# framMega.net
KiCad netlist of a schematic drawn in EAGLE
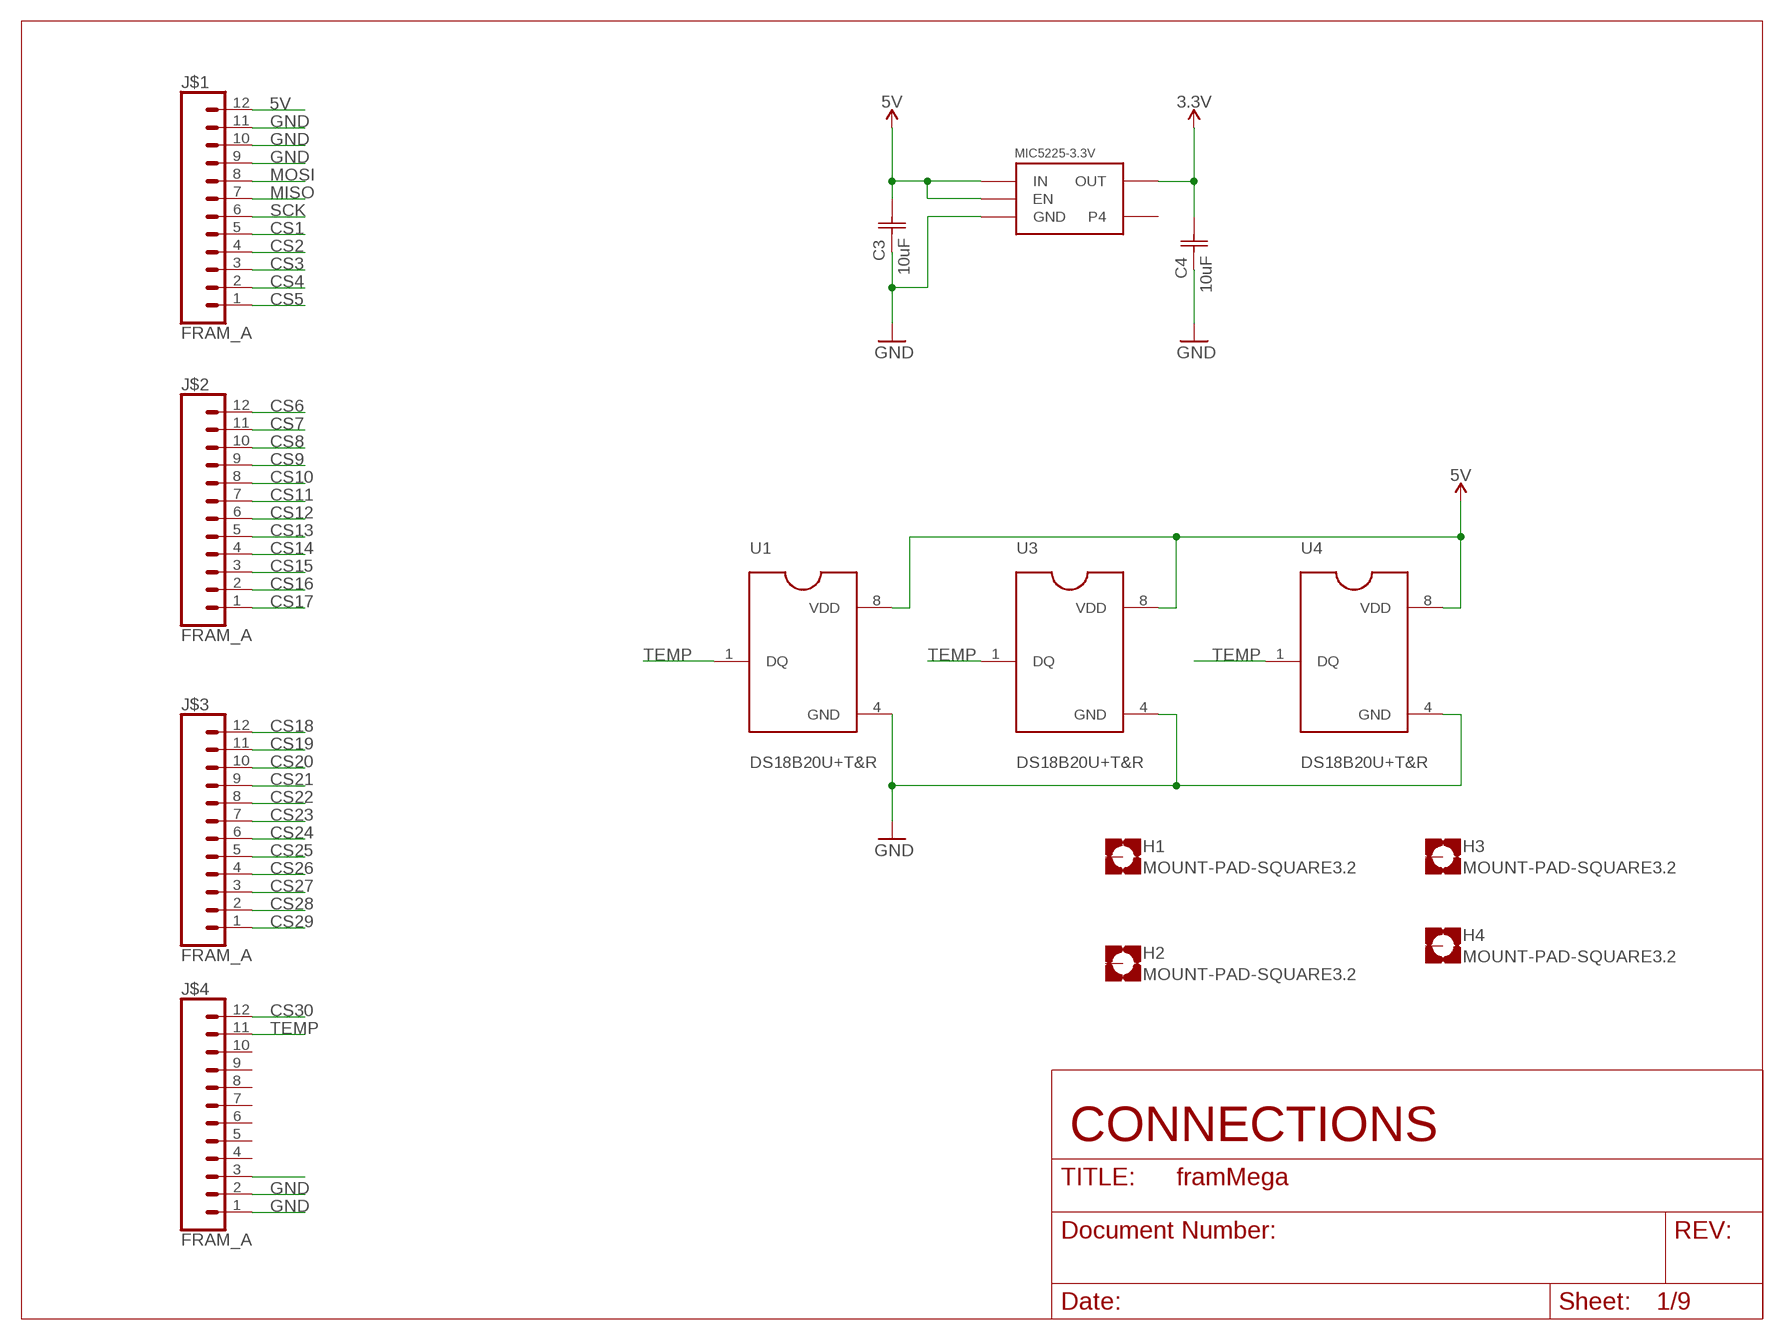
[diagram p0: schematic, sheet 1]
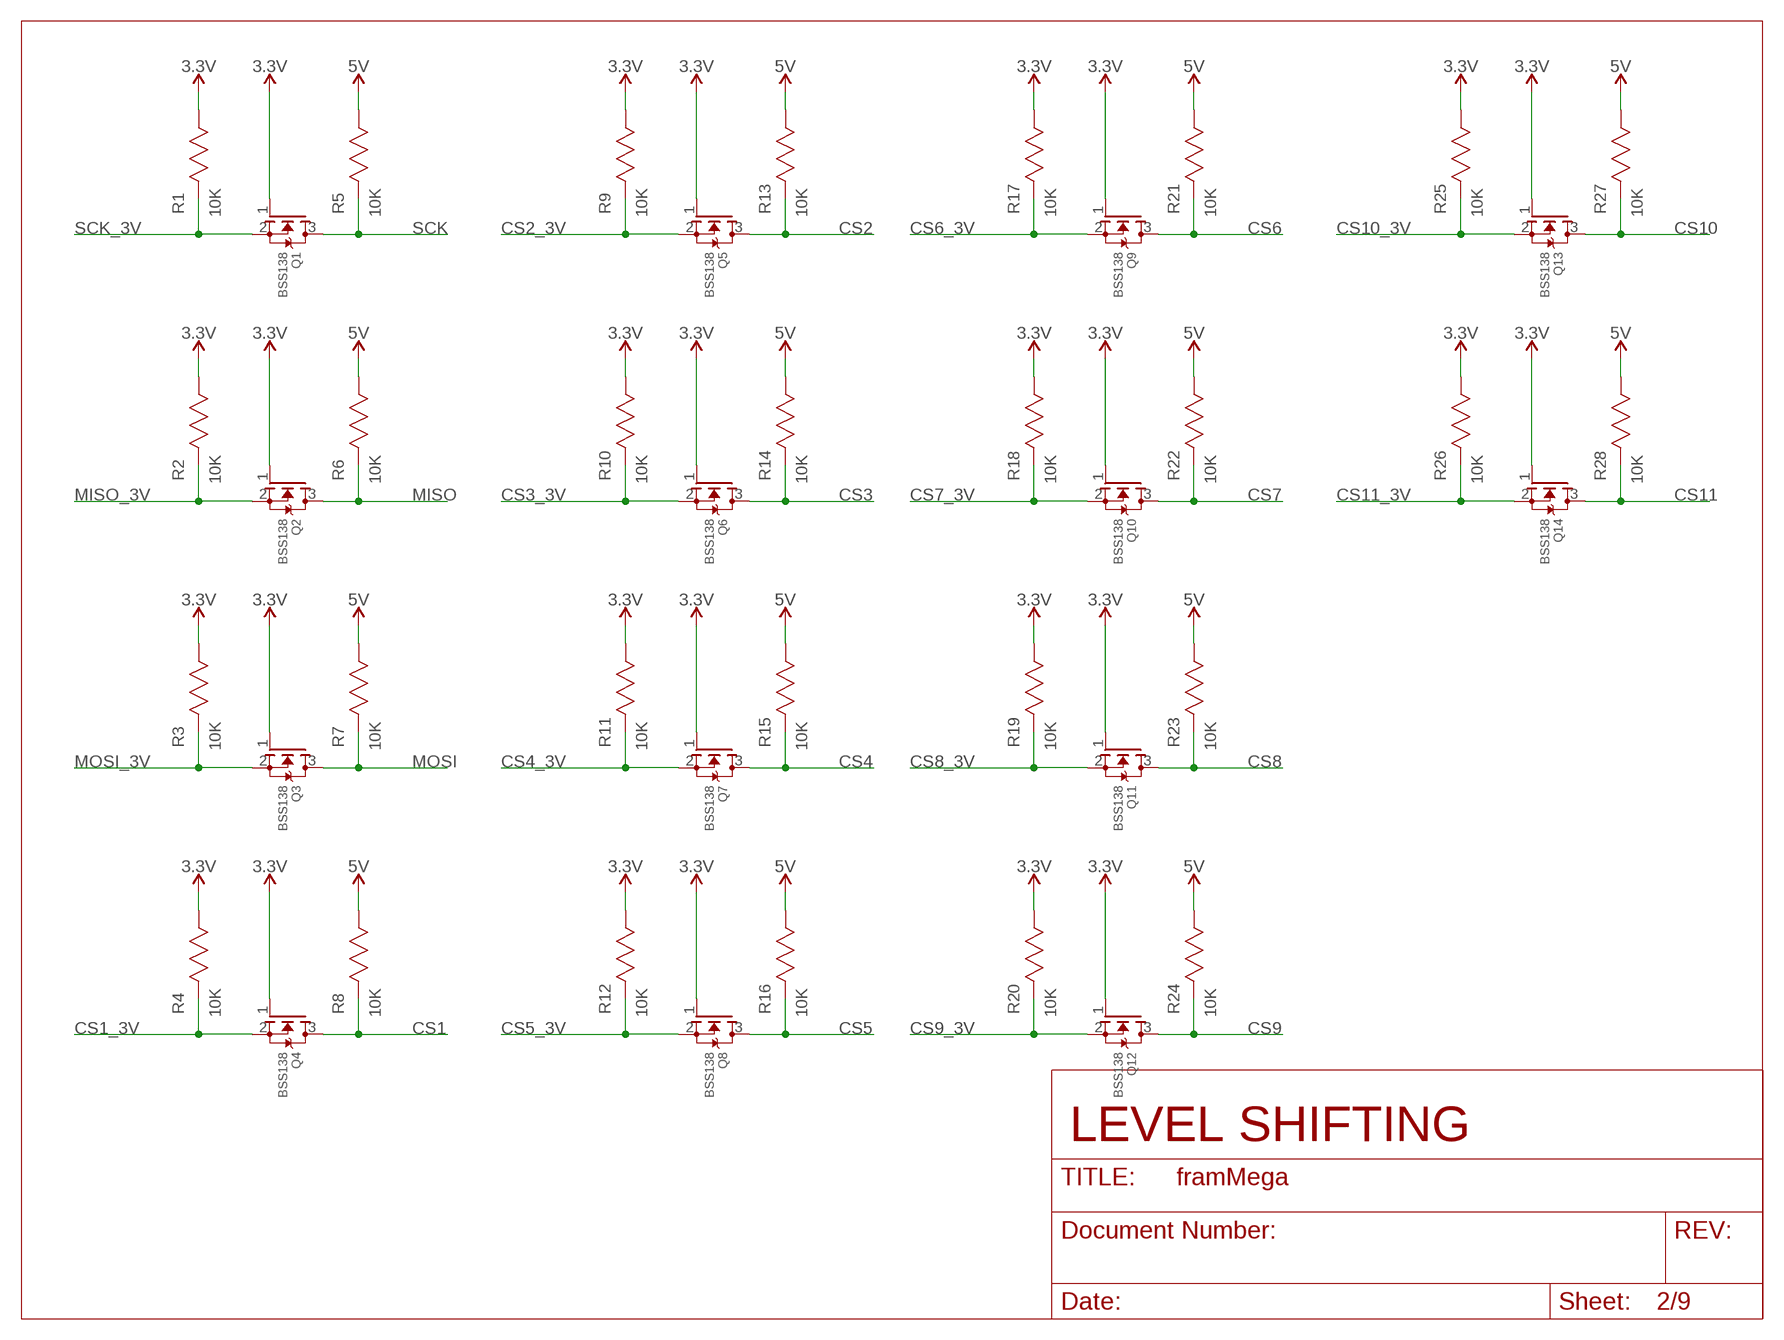
[diagram p1: schematic, sheet 2]
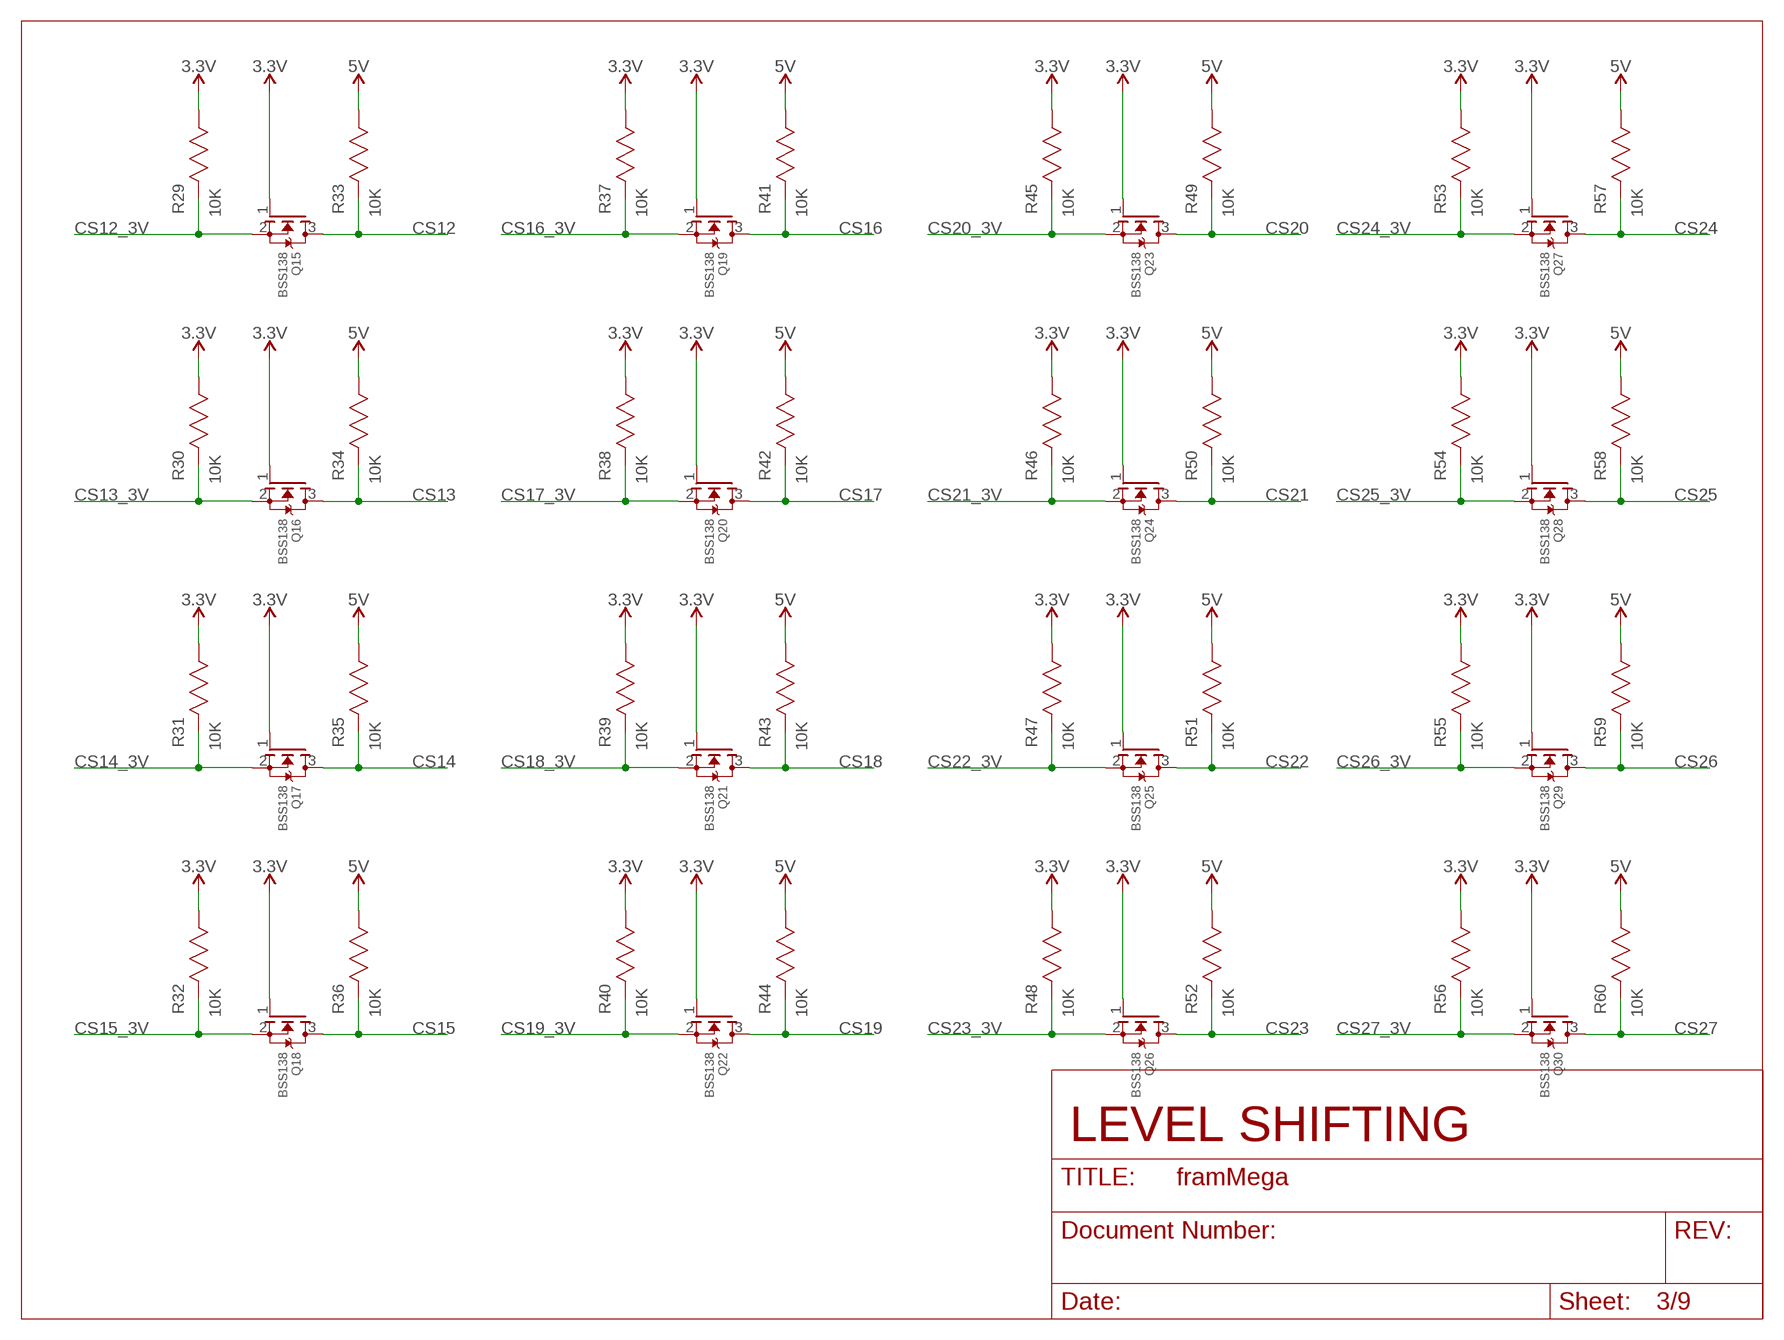
[diagram p2: schematic, sheet 3]
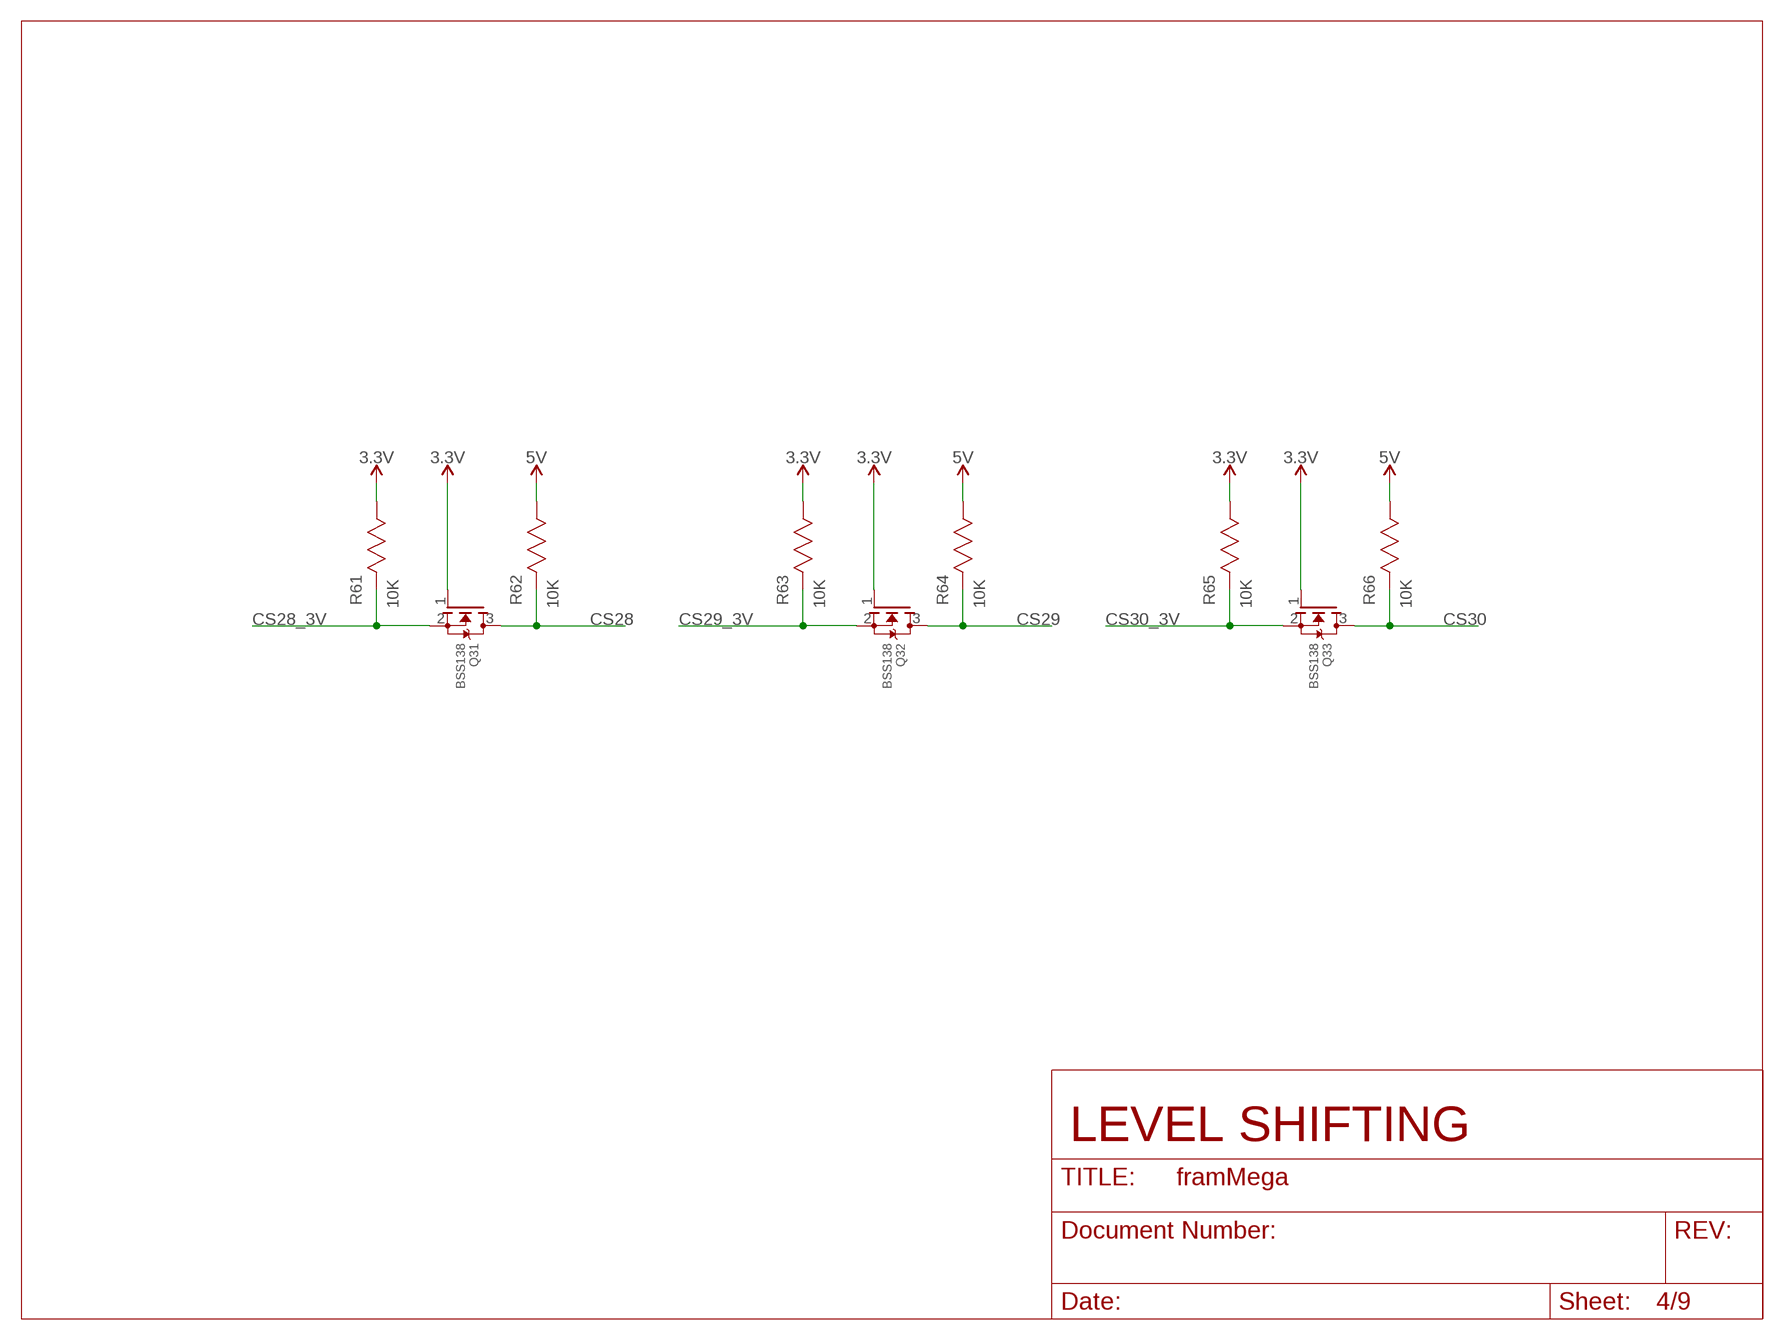
[diagram p3: schematic, sheet 4]
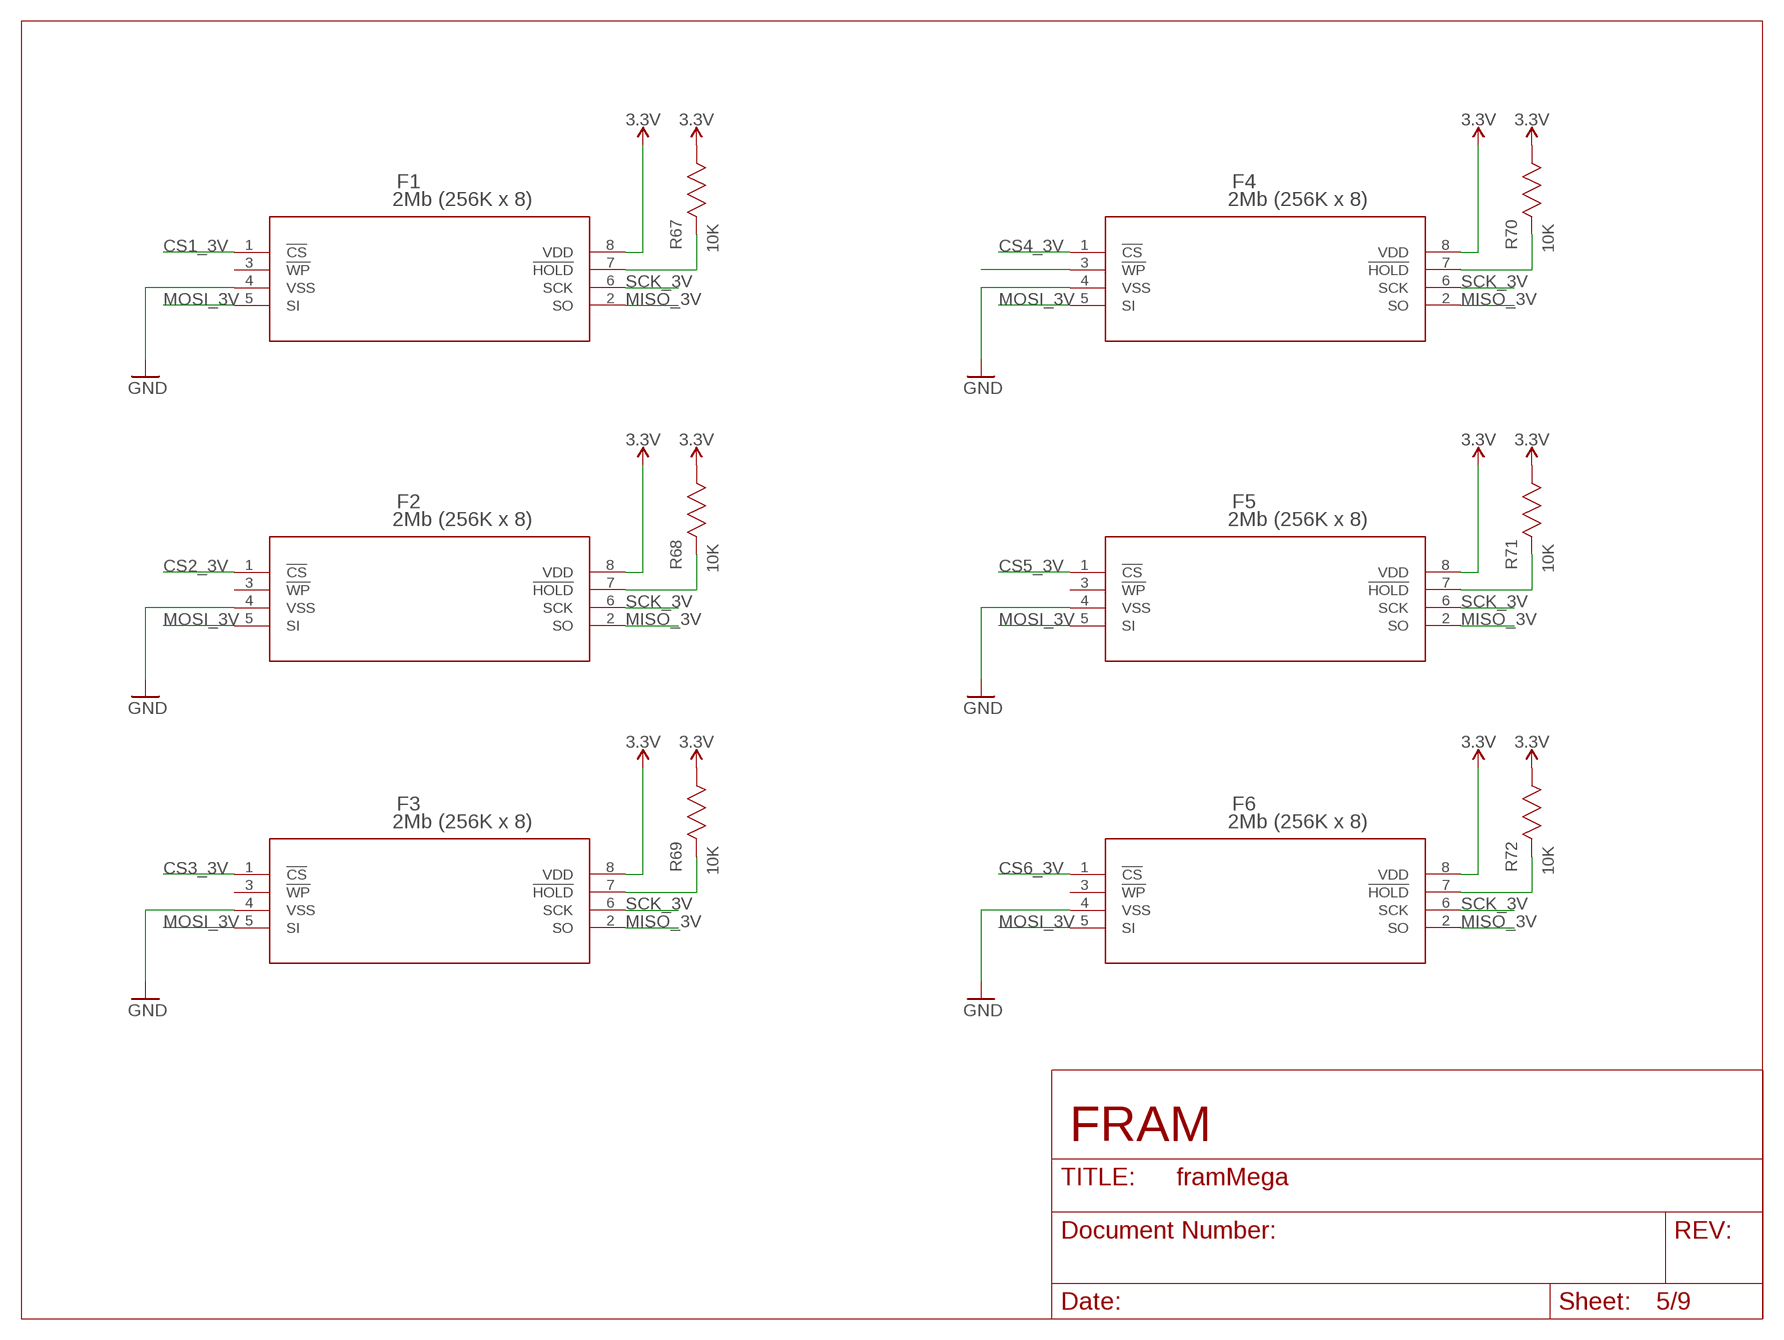
[diagram p4: schematic, sheet 5]
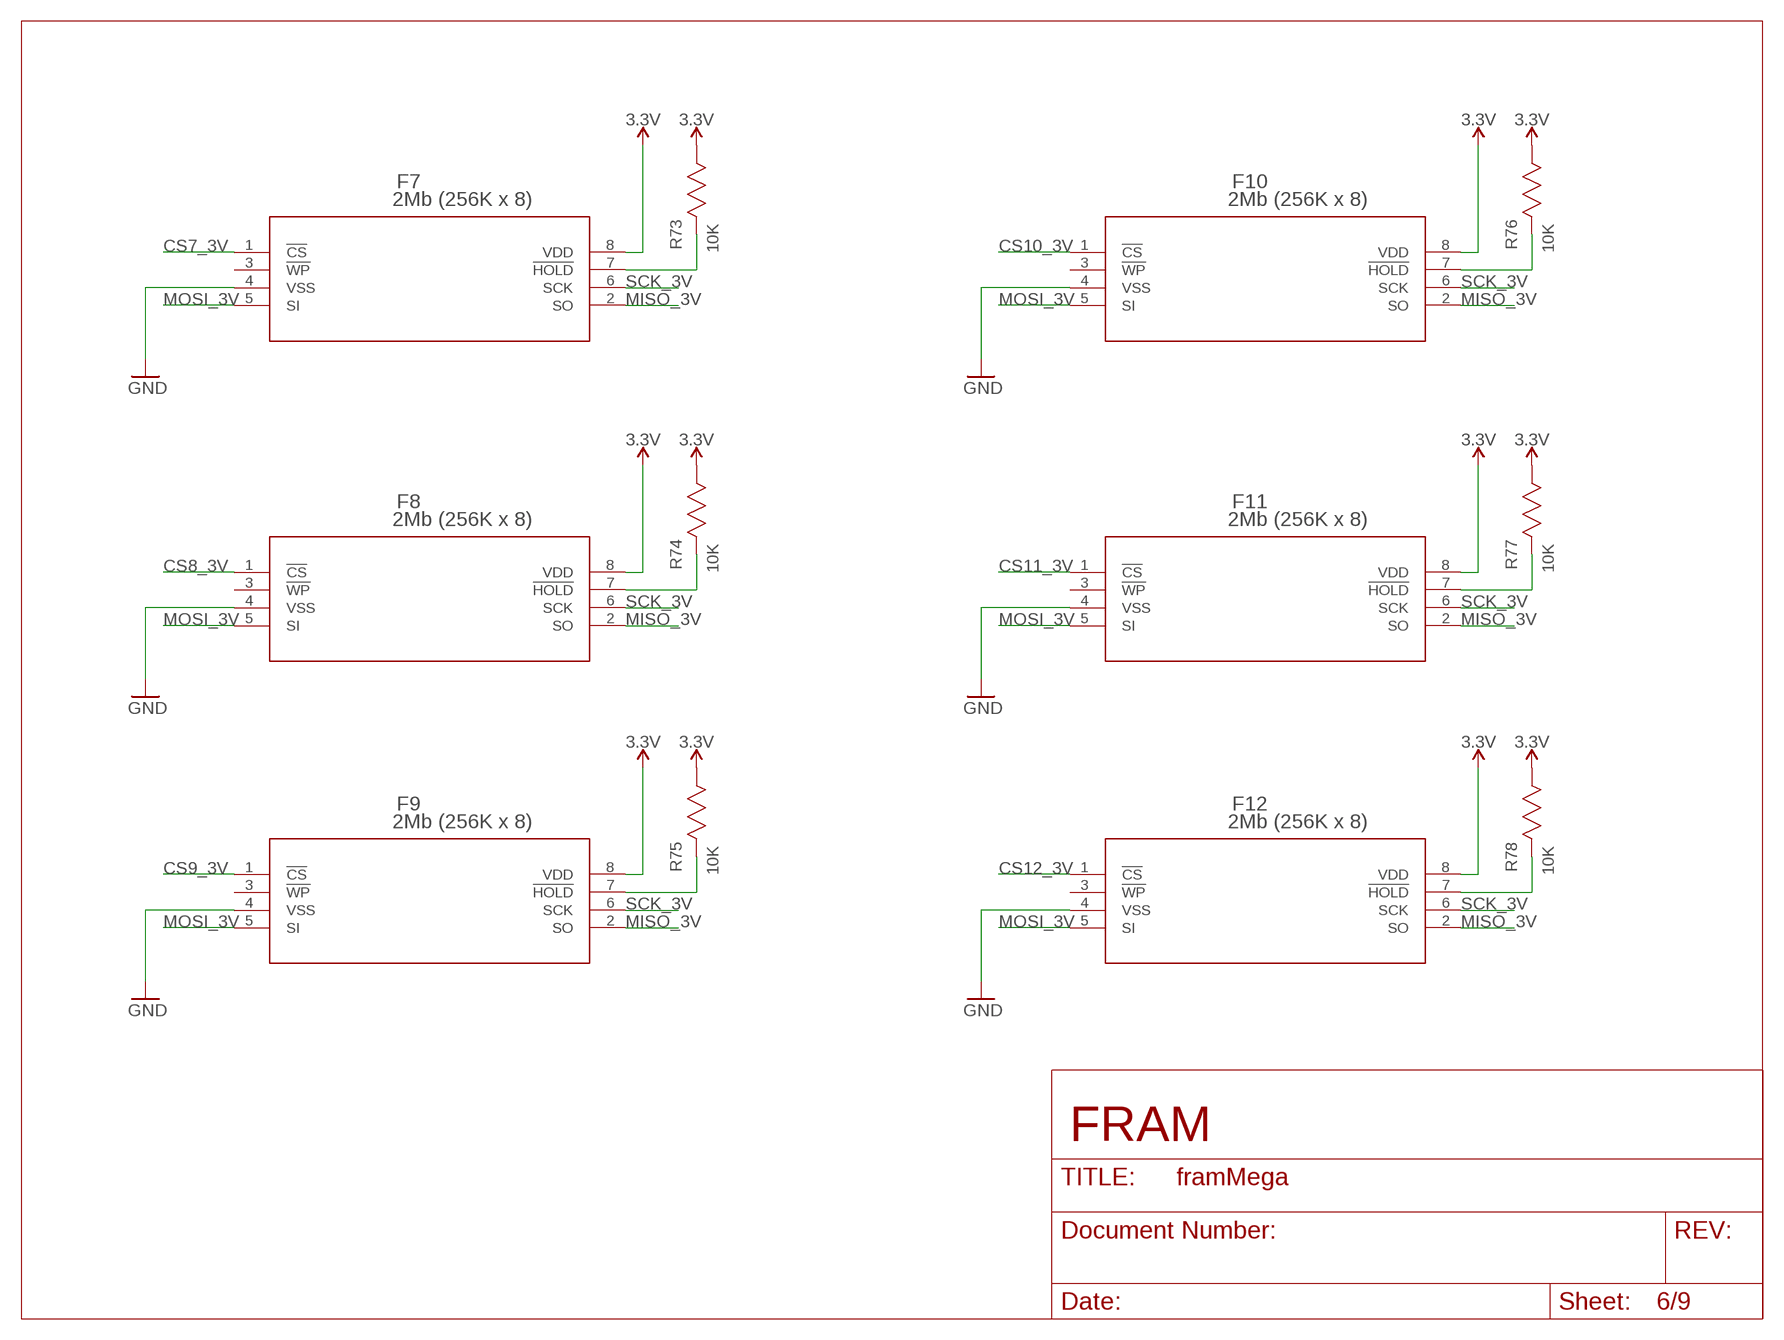
[diagram p5: schematic, sheet 6]
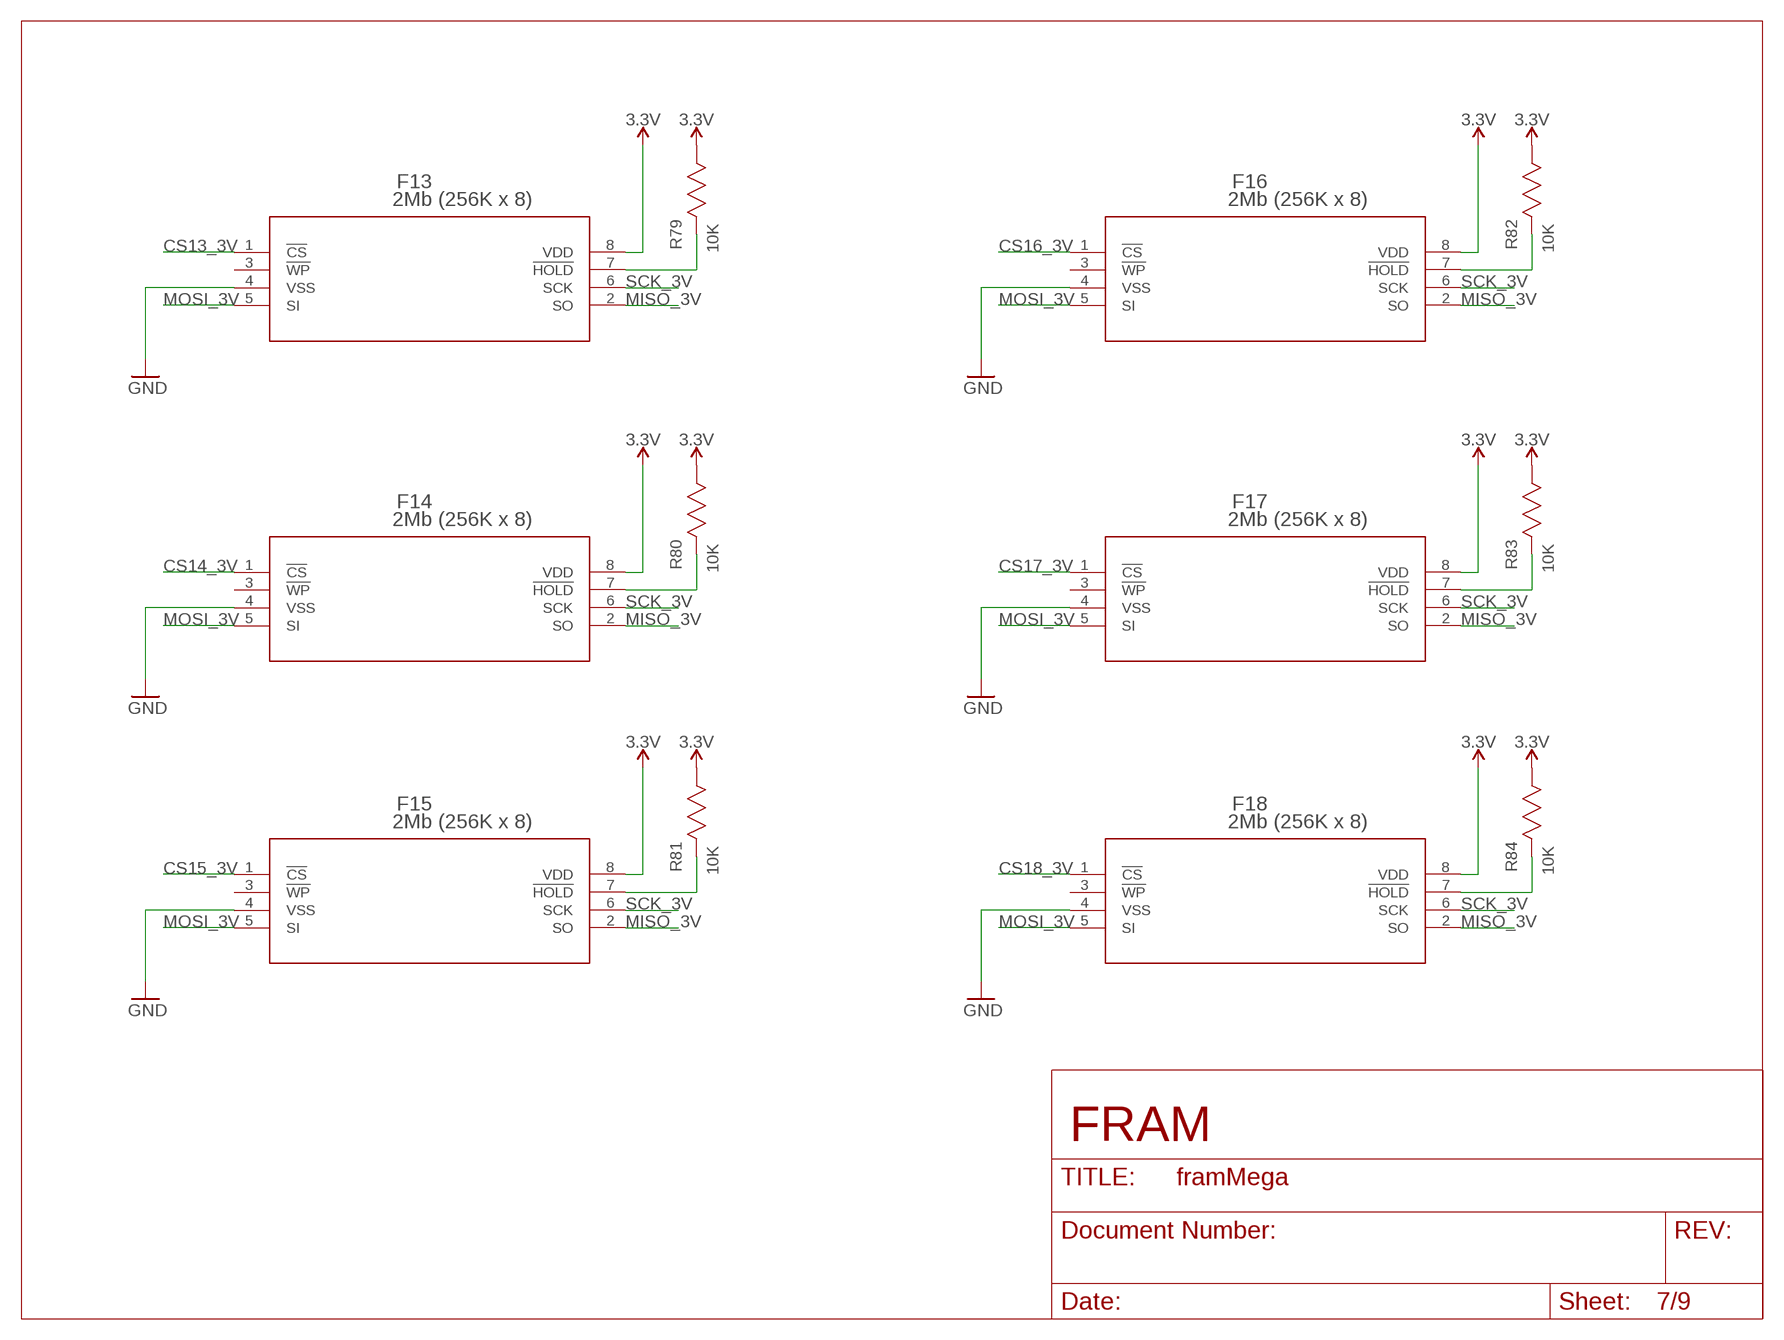
[diagram p6: schematic, sheet 7]
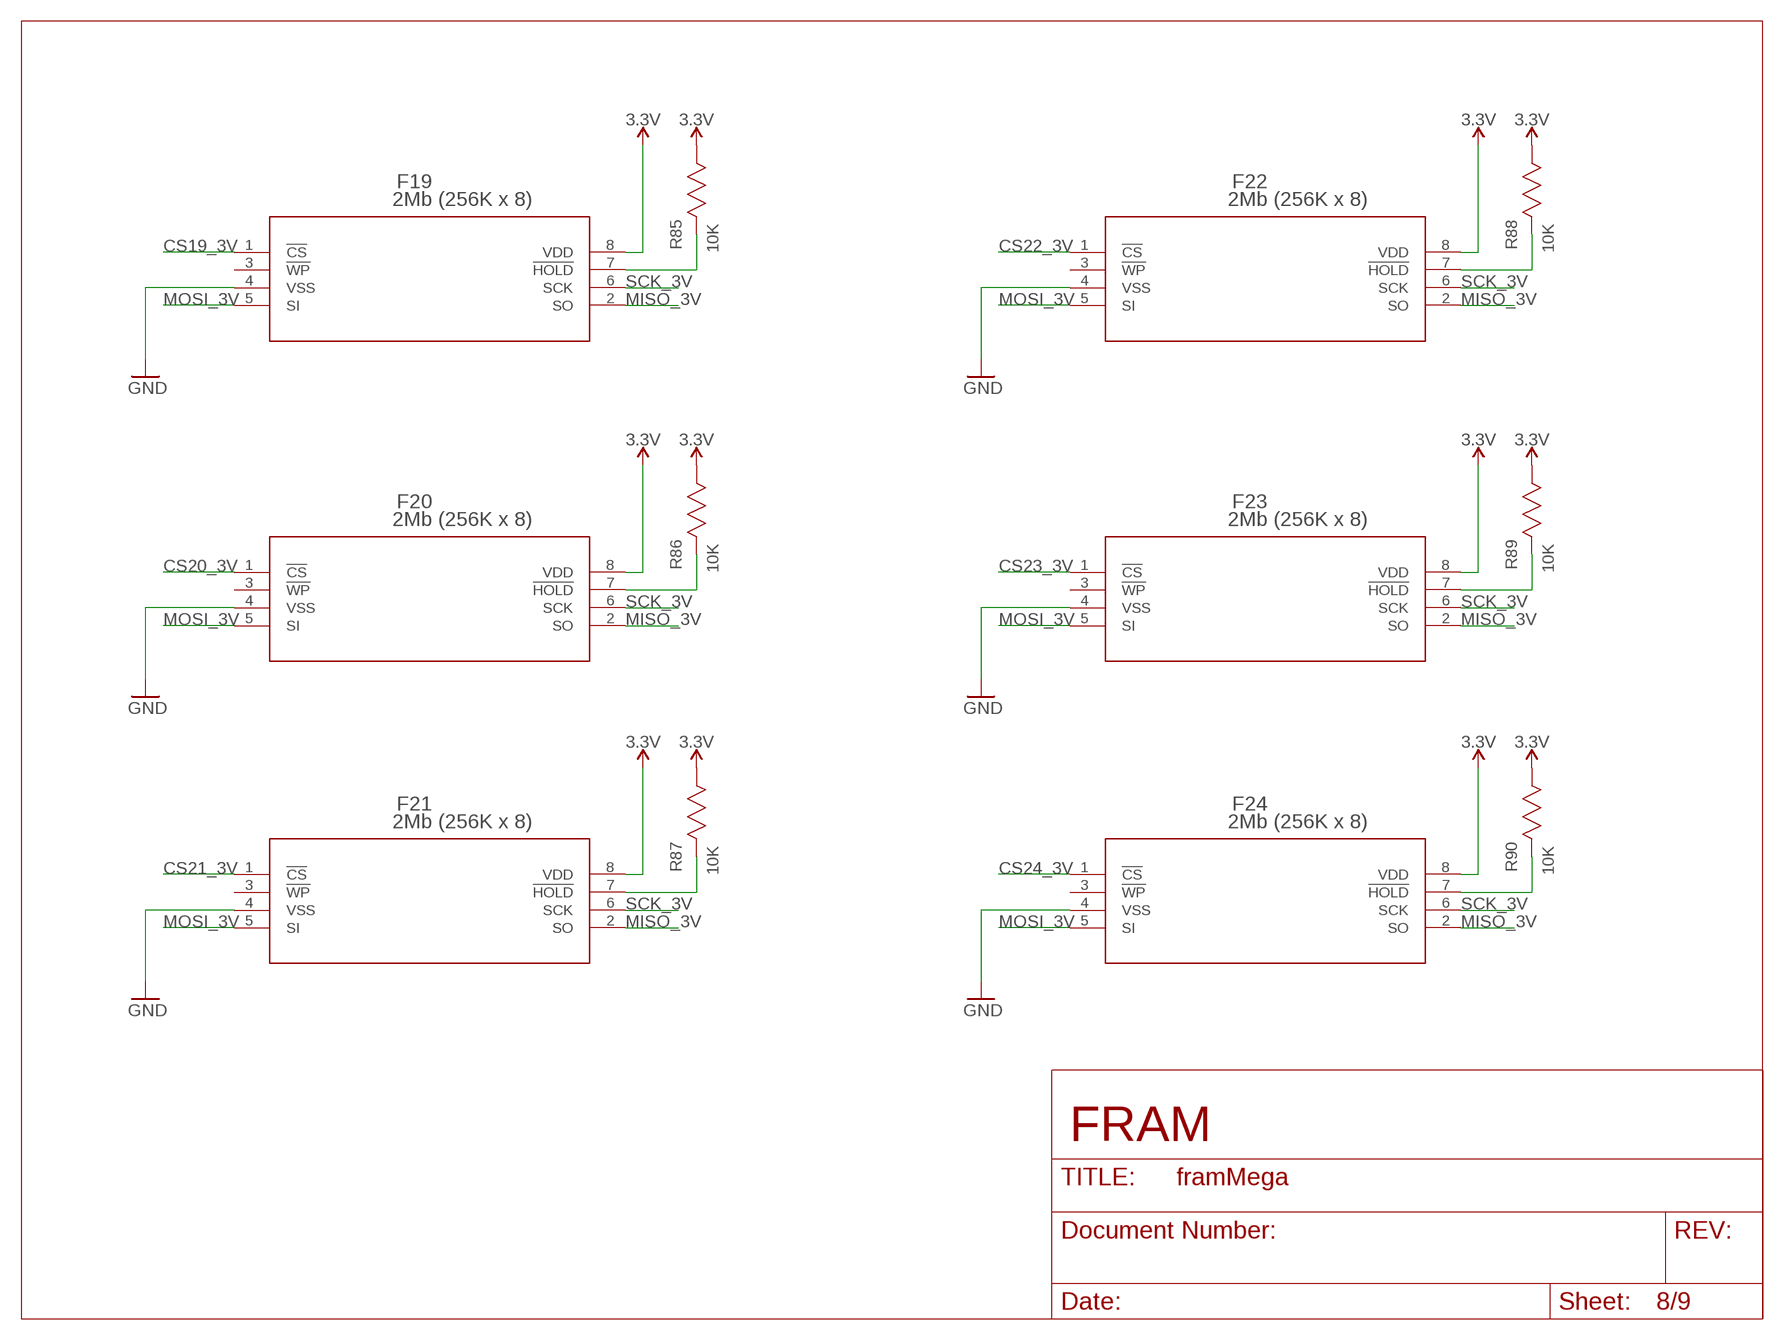
[diagram p7: schematic, sheet 8]
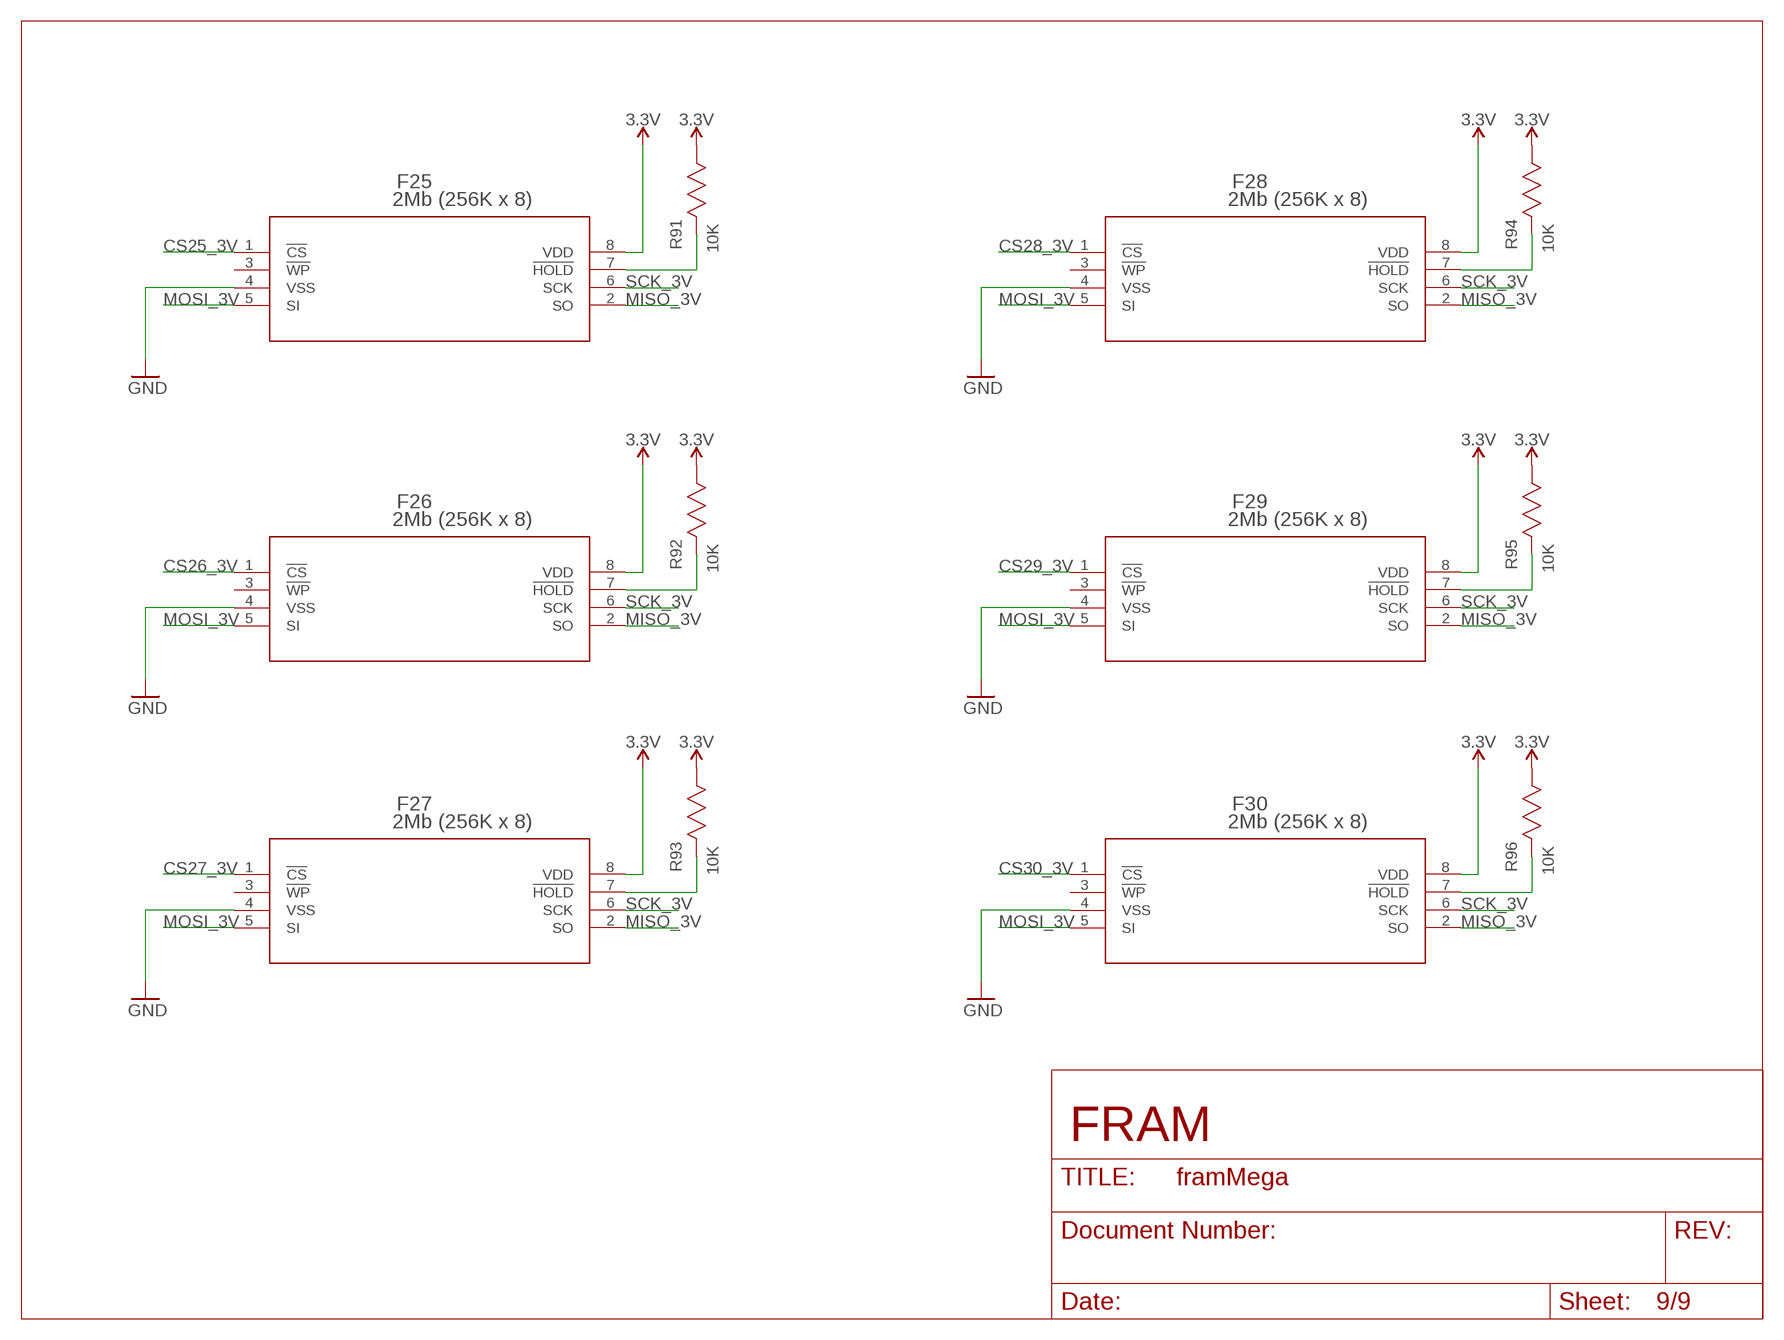
[diagram p8: schematic, sheet 9]

(export (version "E")
  (design (tool "Eeschema 10.0.6"))
  (components
    (comp (ref "Q31")
      (value "BSS138")
      (footprint "eagle-import:SOT23-WIDE")
      (libsource (lib "eagle-import") (part "MOSFET-NWIDE"))
    )
    (comp (ref "Q32")
      (value "BSS138")
      (footprint "eagle-import:SOT23-WIDE")
      (libsource (lib "eagle-import") (part "MOSFET-NWIDE"))
    )
    (comp (ref "Q33")
      (value "BSS138")
      (footprint "eagle-import:SOT23-WIDE")
      (libsource (lib "eagle-import") (part "MOSFET-NWIDE"))
    )
    (comp (ref "R61")
      (value "10K")
      (footprint "eagle-import:RC0603N")
      (libsource (lib "eagle-import") (part "RES_10K"))
    )
    (comp (ref "R62")
      (value "10K")
      (footprint "eagle-import:RC0603N")
      (libsource (lib "eagle-import") (part "RES_10K"))
    )
    (comp (ref "R63")
      (value "10K")
      (footprint "eagle-import:RC0603N")
      (libsource (lib "eagle-import") (part "RES_10K"))
    )
    (comp (ref "R64")
      (value "10K")
      (footprint "eagle-import:RC0603N")
      (libsource (lib "eagle-import") (part "RES_10K"))
    )
    (comp (ref "R65")
      (value "10K")
      (footprint "eagle-import:RC0603N")
      (libsource (lib "eagle-import") (part "RES_10K"))
    )
    (comp (ref "R66")
      (value "10K")
      (footprint "eagle-import:RC0603N")
      (libsource (lib "eagle-import") (part "RES_10K"))
    )
    (comp (ref "Q1")
      (value "BSS138")
      (footprint "eagle-import:SOT23-WIDE")
      (libsource (lib "eagle-import") (part "MOSFET-NWIDE"))
    )
    (comp (ref "Q2")
      (value "BSS138")
      (footprint "eagle-import:SOT23-WIDE")
      (libsource (lib "eagle-import") (part "MOSFET-NWIDE"))
    )
    (comp (ref "Q3")
      (value "BSS138")
      (footprint "eagle-import:SOT23-WIDE")
      (libsource (lib "eagle-import") (part "MOSFET-NWIDE"))
    )
    (comp (ref "Q4")
      (value "BSS138")
      (footprint "eagle-import:SOT23-WIDE")
      (libsource (lib "eagle-import") (part "MOSFET-NWIDE"))
    )
    (comp (ref "Q5")
      (value "BSS138")
      (footprint "eagle-import:SOT23-WIDE")
      (libsource (lib "eagle-import") (part "MOSFET-NWIDE"))
    )
    (comp (ref "Q6")
      (value "BSS138")
      (footprint "eagle-import:SOT23-WIDE")
      (libsource (lib "eagle-import") (part "MOSFET-NWIDE"))
    )
    (comp (ref "Q7")
      (value "BSS138")
      (footprint "eagle-import:SOT23-WIDE")
      (libsource (lib "eagle-import") (part "MOSFET-NWIDE"))
    )
    (comp (ref "Q8")
      (value "BSS138")
      (footprint "eagle-import:SOT23-WIDE")
      (libsource (lib "eagle-import") (part "MOSFET-NWIDE"))
    )
    (comp (ref "Q9")
      (value "BSS138")
      (footprint "eagle-import:SOT23-WIDE")
      (libsource (lib "eagle-import") (part "MOSFET-NWIDE"))
    )
    (comp (ref "Q10")
      (value "BSS138")
      (footprint "eagle-import:SOT23-WIDE")
      (libsource (lib "eagle-import") (part "MOSFET-NWIDE"))
    )
    (comp (ref "Q11")
      (value "BSS138")
      (footprint "eagle-import:SOT23-WIDE")
      (libsource (lib "eagle-import") (part "MOSFET-NWIDE"))
    )
    (comp (ref "Q12")
      (value "BSS138")
      (footprint "eagle-import:SOT23-WIDE")
      (libsource (lib "eagle-import") (part "MOSFET-NWIDE"))
    )
    (comp (ref "Q13")
      (value "BSS138")
      (footprint "eagle-import:SOT23-WIDE")
      (libsource (lib "eagle-import") (part "MOSFET-NWIDE"))
    )
    (comp (ref "Q14")
      (value "BSS138")
      (footprint "eagle-import:SOT23-WIDE")
      (libsource (lib "eagle-import") (part "MOSFET-NWIDE"))
    )
    (comp (ref "R1")
      (value "10K")
      (footprint "eagle-import:RC0603N")
      (libsource (lib "eagle-import") (part "RES_10K"))
    )
    (comp (ref "R2")
      (value "10K")
      (footprint "eagle-import:RC0603N")
      (libsource (lib "eagle-import") (part "RES_10K"))
    )
    (comp (ref "R3")
      (value "10K")
      (footprint "eagle-import:RC0603N")
      (libsource (lib "eagle-import") (part "RES_10K"))
    )
    (comp (ref "R4")
      (value "10K")
      (footprint "eagle-import:RC0603N")
      (libsource (lib "eagle-import") (part "RES_10K"))
    )
    (comp (ref "R5")
      (value "10K")
      (footprint "eagle-import:RC0603N")
      (libsource (lib "eagle-import") (part "RES_10K"))
    )
    (comp (ref "R6")
      (value "10K")
      (footprint "eagle-import:RC0603N")
      (libsource (lib "eagle-import") (part "RES_10K"))
    )
    (comp (ref "R7")
      (value "10K")
      (footprint "eagle-import:RC0603N")
      (libsource (lib "eagle-import") (part "RES_10K"))
    )
    (comp (ref "R8")
      (value "10K")
      (footprint "eagle-import:RC0603N")
      (libsource (lib "eagle-import") (part "RES_10K"))
    )
    (comp (ref "R9")
      (value "10K")
      (footprint "eagle-import:RC0603N")
      (libsource (lib "eagle-import") (part "RES_10K"))
    )
    (comp (ref "R10")
      (value "10K")
      (footprint "eagle-import:RC0603N")
      (libsource (lib "eagle-import") (part "RES_10K"))
    )
    (comp (ref "R11")
      (value "10K")
      (footprint "eagle-import:RC0603N")
      (libsource (lib "eagle-import") (part "RES_10K"))
    )
    (comp (ref "R12")
      (value "10K")
      (footprint "eagle-import:RC0603N")
      (libsource (lib "eagle-import") (part "RES_10K"))
    )
    (comp (ref "R13")
      (value "10K")
      (footprint "eagle-import:RC0603N")
      (libsource (lib "eagle-import") (part "RES_10K"))
    )
    (comp (ref "R14")
      (value "10K")
      (footprint "eagle-import:RC0603N")
      (libsource (lib "eagle-import") (part "RES_10K"))
    )
    (comp (ref "R15")
      (value "10K")
      (footprint "eagle-import:RC0603N")
      (libsource (lib "eagle-import") (part "RES_10K"))
    )
    (comp (ref "R16")
      (value "10K")
      (footprint "eagle-import:RC0603N")
      (libsource (lib "eagle-import") (part "RES_10K"))
    )
    (comp (ref "R17")
      (value "10K")
      (footprint "eagle-import:RC0603N")
      (libsource (lib "eagle-import") (part "RES_10K"))
    )
    (comp (ref "R18")
      (value "10K")
      (footprint "eagle-import:RC0603N")
      (libsource (lib "eagle-import") (part "RES_10K"))
    )
    (comp (ref "R19")
      (value "10K")
      (footprint "eagle-import:RC0603N")
      (libsource (lib "eagle-import") (part "RES_10K"))
    )
    (comp (ref "R20")
      (value "10K")
      (footprint "eagle-import:RC0603N")
      (libsource (lib "eagle-import") (part "RES_10K"))
    )
    (comp (ref "R21")
      (value "10K")
      (footprint "eagle-import:RC0603N")
      (libsource (lib "eagle-import") (part "RES_10K"))
    )
    (comp (ref "R22")
      (value "10K")
      (footprint "eagle-import:RC0603N")
      (libsource (lib "eagle-import") (part "RES_10K"))
    )
    (comp (ref "R23")
      (value "10K")
      (footprint "eagle-import:RC0603N")
      (libsource (lib "eagle-import") (part "RES_10K"))
    )
    (comp (ref "R24")
      (value "10K")
      (footprint "eagle-import:RC0603N")
      (libsource (lib "eagle-import") (part "RES_10K"))
    )
    (comp (ref "R25")
      (value "10K")
      (footprint "eagle-import:RC0603N")
      (libsource (lib "eagle-import") (part "RES_10K"))
    )
    (comp (ref "R26")
      (value "10K")
      (footprint "eagle-import:RC0603N")
      (libsource (lib "eagle-import") (part "RES_10K"))
    )
    (comp (ref "R27")
      (value "10K")
      (footprint "eagle-import:RC0603N")
      (libsource (lib "eagle-import") (part "RES_10K"))
    )
    (comp (ref "R28")
      (value "10K")
      (footprint "eagle-import:RC0603N")
      (libsource (lib "eagle-import") (part "RES_10K"))
    )
    (comp (ref "F19")
      (value "2Mb (256K x 8)")
      (footprint "eagle-import:FRAM_MB85RS2MTA_FPT-8P-M09")
      (libsource (lib "eagle-import") (part "FRAM_MB85RS2MTA"))
    )
    (comp (ref "F20")
      (value "2Mb (256K x 8)")
      (footprint "eagle-import:FRAM_MB85RS2MTA_FPT-8P-M09")
      (libsource (lib "eagle-import") (part "FRAM_MB85RS2MTA"))
    )
    (comp (ref "F21")
      (value "2Mb (256K x 8)")
      (footprint "eagle-import:FRAM_MB85RS2MTA_FPT-8P-M09")
      (libsource (lib "eagle-import") (part "FRAM_MB85RS2MTA"))
    )
    (comp (ref "F22")
      (value "2Mb (256K x 8)")
      (footprint "eagle-import:FRAM_MB85RS2MTA_FPT-8P-M09")
      (libsource (lib "eagle-import") (part "FRAM_MB85RS2MTA"))
    )
    (comp (ref "F23")
      (value "2Mb (256K x 8)")
      (footprint "eagle-import:FRAM_MB85RS2MTA_FPT-8P-M09")
      (libsource (lib "eagle-import") (part "FRAM_MB85RS2MTA"))
    )
    (comp (ref "F24")
      (value "2Mb (256K x 8)")
      (footprint "eagle-import:FRAM_MB85RS2MTA_FPT-8P-M09")
      (libsource (lib "eagle-import") (part "FRAM_MB85RS2MTA"))
    )
    (comp (ref "R85")
      (value "10K")
      (footprint "eagle-import:RC0603N")
      (libsource (lib "eagle-import") (part "RES_10K"))
    )
    (comp (ref "R86")
      (value "10K")
      (footprint "eagle-import:RC0603N")
      (libsource (lib "eagle-import") (part "RES_10K"))
    )
    (comp (ref "R87")
      (value "10K")
      (footprint "eagle-import:RC0603N")
      (libsource (lib "eagle-import") (part "RES_10K"))
    )
    (comp (ref "R88")
      (value "10K")
      (footprint "eagle-import:RC0603N")
      (libsource (lib "eagle-import") (part "RES_10K"))
    )
    (comp (ref "R89")
      (value "10K")
      (footprint "eagle-import:RC0603N")
      (libsource (lib "eagle-import") (part "RES_10K"))
    )
    (comp (ref "R90")
      (value "10K")
      (footprint "eagle-import:RC0603N")
      (libsource (lib "eagle-import") (part "RES_10K"))
    )
    (comp (ref "Q15")
      (value "BSS138")
      (footprint "eagle-import:SOT23-WIDE")
      (libsource (lib "eagle-import") (part "MOSFET-NWIDE"))
    )
    (comp (ref "Q16")
      (value "BSS138")
      (footprint "eagle-import:SOT23-WIDE")
      (libsource (lib "eagle-import") (part "MOSFET-NWIDE"))
    )
    (comp (ref "Q17")
      (value "BSS138")
      (footprint "eagle-import:SOT23-WIDE")
      (libsource (lib "eagle-import") (part "MOSFET-NWIDE"))
    )
    (comp (ref "Q18")
      (value "BSS138")
      (footprint "eagle-import:SOT23-WIDE")
      (libsource (lib "eagle-import") (part "MOSFET-NWIDE"))
    )
    (comp (ref "Q19")
      (value "BSS138")
      (footprint "eagle-import:SOT23-WIDE")
      (libsource (lib "eagle-import") (part "MOSFET-NWIDE"))
    )
    (comp (ref "Q20")
      (value "BSS138")
      (footprint "eagle-import:SOT23-WIDE")
      (libsource (lib "eagle-import") (part "MOSFET-NWIDE"))
    )
    (comp (ref "Q21")
      (value "BSS138")
      (footprint "eagle-import:SOT23-WIDE")
      (libsource (lib "eagle-import") (part "MOSFET-NWIDE"))
    )
    (comp (ref "Q22")
      (value "BSS138")
      (footprint "eagle-import:SOT23-WIDE")
      (libsource (lib "eagle-import") (part "MOSFET-NWIDE"))
    )
    (comp (ref "Q23")
      (value "BSS138")
      (footprint "eagle-import:SOT23-WIDE")
      (libsource (lib "eagle-import") (part "MOSFET-NWIDE"))
    )
    (comp (ref "Q24")
      (value "BSS138")
      (footprint "eagle-import:SOT23-WIDE")
      (libsource (lib "eagle-import") (part "MOSFET-NWIDE"))
    )
    (comp (ref "Q25")
      (value "BSS138")
      (footprint "eagle-import:SOT23-WIDE")
      (libsource (lib "eagle-import") (part "MOSFET-NWIDE"))
    )
    (comp (ref "Q26")
      (value "BSS138")
      (footprint "eagle-import:SOT23-WIDE")
      (libsource (lib "eagle-import") (part "MOSFET-NWIDE"))
    )
    (comp (ref "Q27")
      (value "BSS138")
      (footprint "eagle-import:SOT23-WIDE")
      (libsource (lib "eagle-import") (part "MOSFET-NWIDE"))
    )
    (comp (ref "Q28")
      (value "BSS138")
      (footprint "eagle-import:SOT23-WIDE")
      (libsource (lib "eagle-import") (part "MOSFET-NWIDE"))
    )
    (comp (ref "Q29")
      (value "BSS138")
      (footprint "eagle-import:SOT23-WIDE")
      (libsource (lib "eagle-import") (part "MOSFET-NWIDE"))
    )
    (comp (ref "Q30")
      (value "BSS138")
      (footprint "eagle-import:SOT23-WIDE")
      (libsource (lib "eagle-import") (part "MOSFET-NWIDE"))
    )
    (comp (ref "R29")
      (value "10K")
      (footprint "eagle-import:RC0603N")
      (libsource (lib "eagle-import") (part "RES_10K"))
    )
    (comp (ref "R30")
      (value "10K")
      (footprint "eagle-import:RC0603N")
      (libsource (lib "eagle-import") (part "RES_10K"))
    )
    (comp (ref "R31")
      (value "10K")
      (footprint "eagle-import:RC0603N")
      (libsource (lib "eagle-import") (part "RES_10K"))
    )
    (comp (ref "R32")
      (value "10K")
      (footprint "eagle-import:RC0603N")
      (libsource (lib "eagle-import") (part "RES_10K"))
    )
    (comp (ref "R33")
      (value "10K")
      (footprint "eagle-import:RC0603N")
      (libsource (lib "eagle-import") (part "RES_10K"))
    )
    (comp (ref "R34")
      (value "10K")
      (footprint "eagle-import:RC0603N")
      (libsource (lib "eagle-import") (part "RES_10K"))
    )
    (comp (ref "R35")
      (value "10K")
      (footprint "eagle-import:RC0603N")
      (libsource (lib "eagle-import") (part "RES_10K"))
    )
    (comp (ref "R36")
      (value "10K")
      (footprint "eagle-import:RC0603N")
      (libsource (lib "eagle-import") (part "RES_10K"))
    )
    (comp (ref "R37")
      (value "10K")
      (footprint "eagle-import:RC0603N")
      (libsource (lib "eagle-import") (part "RES_10K"))
    )
    (comp (ref "R38")
      (value "10K")
      (footprint "eagle-import:RC0603N")
      (libsource (lib "eagle-import") (part "RES_10K"))
    )
    (comp (ref "R39")
      (value "10K")
      (footprint "eagle-import:RC0603N")
      (libsource (lib "eagle-import") (part "RES_10K"))
    )
    (comp (ref "R40")
      (value "10K")
      (footprint "eagle-import:RC0603N")
      (libsource (lib "eagle-import") (part "RES_10K"))
    )
    (comp (ref "R41")
      (value "10K")
      (footprint "eagle-import:RC0603N")
      (libsource (lib "eagle-import") (part "RES_10K"))
    )
    (comp (ref "R42")
      (value "10K")
      (footprint "eagle-import:RC0603N")
      (libsource (lib "eagle-import") (part "RES_10K"))
    )
    (comp (ref "R43")
      (value "10K")
      (footprint "eagle-import:RC0603N")
      (libsource (lib "eagle-import") (part "RES_10K"))
    )
    (comp (ref "R44")
      (value "10K")
      (footprint "eagle-import:RC0603N")
      (libsource (lib "eagle-import") (part "RES_10K"))
    )
    (comp (ref "R45")
      (value "10K")
      (footprint "eagle-import:RC0603N")
      (libsource (lib "eagle-import") (part "RES_10K"))
    )
    (comp (ref "R46")
      (value "10K")
      (footprint "eagle-import:RC0603N")
      (libsource (lib "eagle-import") (part "RES_10K"))
    )
    (comp (ref "R47")
      (value "10K")
      (footprint "eagle-import:RC0603N")
      (libsource (lib "eagle-import") (part "RES_10K"))
    )
    (comp (ref "R48")
      (value "10K")
      (footprint "eagle-import:RC0603N")
      (libsource (lib "eagle-import") (part "RES_10K"))
    )
    (comp (ref "R49")
      (value "10K")
      (footprint "eagle-import:RC0603N")
      (libsource (lib "eagle-import") (part "RES_10K"))
    )
    (comp (ref "R50")
      (value "10K")
      (footprint "eagle-import:RC0603N")
      (libsource (lib "eagle-import") (part "RES_10K"))
    )
    (comp (ref "R51")
      (value "10K")
      (footprint "eagle-import:RC0603N")
      (libsource (lib "eagle-import") (part "RES_10K"))
    )
    (comp (ref "R52")
      (value "10K")
      (footprint "eagle-import:RC0603N")
      (libsource (lib "eagle-import") (part "RES_10K"))
    )
    (comp (ref "R53")
      (value "10K")
      (footprint "eagle-import:RC0603N")
      (libsource (lib "eagle-import") (part "RES_10K"))
    )
    (comp (ref "R54")
      (value "10K")
      (footprint "eagle-import:RC0603N")
      (libsource (lib "eagle-import") (part "RES_10K"))
    )
    (comp (ref "R55")
      (value "10K")
      (footprint "eagle-import:RC0603N")
      (libsource (lib "eagle-import") (part "RES_10K"))
    )
    (comp (ref "R56")
      (value "10K")
      (footprint "eagle-import:RC0603N")
      (libsource (lib "eagle-import") (part "RES_10K"))
    )
    (comp (ref "R57")
      (value "10K")
      (footprint "eagle-import:RC0603N")
      (libsource (lib "eagle-import") (part "RES_10K"))
    )
    (comp (ref "R58")
      (value "10K")
      (footprint "eagle-import:RC0603N")
      (libsource (lib "eagle-import") (part "RES_10K"))
    )
    (comp (ref "R59")
      (value "10K")
      (footprint "eagle-import:RC0603N")
      (libsource (lib "eagle-import") (part "RES_10K"))
    )
    (comp (ref "R60")
      (value "10K")
      (footprint "eagle-import:RC0603N")
      (libsource (lib "eagle-import") (part "RES_10K"))
    )
    (comp (ref "F13")
      (value "2Mb (256K x 8)")
      (footprint "eagle-import:FRAM_MB85RS2MTA_FPT-8P-M09")
      (libsource (lib "eagle-import") (part "FRAM_MB85RS2MTA"))
    )
    (comp (ref "F14")
      (value "2Mb (256K x 8)")
      (footprint "eagle-import:FRAM_MB85RS2MTA_FPT-8P-M09")
      (libsource (lib "eagle-import") (part "FRAM_MB85RS2MTA"))
    )
    (comp (ref "F15")
      (value "2Mb (256K x 8)")
      (footprint "eagle-import:FRAM_MB85RS2MTA_FPT-8P-M09")
      (libsource (lib "eagle-import") (part "FRAM_MB85RS2MTA"))
    )
    (comp (ref "F16")
      (value "2Mb (256K x 8)")
      (footprint "eagle-import:FRAM_MB85RS2MTA_FPT-8P-M09")
      (libsource (lib "eagle-import") (part "FRAM_MB85RS2MTA"))
    )
    (comp (ref "F17")
      (value "2Mb (256K x 8)")
      (footprint "eagle-import:FRAM_MB85RS2MTA_FPT-8P-M09")
      (libsource (lib "eagle-import") (part "FRAM_MB85RS2MTA"))
    )
    (comp (ref "F18")
      (value "2Mb (256K x 8)")
      (footprint "eagle-import:FRAM_MB85RS2MTA_FPT-8P-M09")
      (libsource (lib "eagle-import") (part "FRAM_MB85RS2MTA"))
    )
    (comp (ref "R79")
      (value "10K")
      (footprint "eagle-import:RC0603N")
      (libsource (lib "eagle-import") (part "RES_10K"))
    )
    (comp (ref "R80")
      (value "10K")
      (footprint "eagle-import:RC0603N")
      (libsource (lib "eagle-import") (part "RES_10K"))
    )
    (comp (ref "R81")
      (value "10K")
      (footprint "eagle-import:RC0603N")
      (libsource (lib "eagle-import") (part "RES_10K"))
    )
    (comp (ref "R82")
      (value "10K")
      (footprint "eagle-import:RC0603N")
      (libsource (lib "eagle-import") (part "RES_10K"))
    )
    (comp (ref "R83")
      (value "10K")
      (footprint "eagle-import:RC0603N")
      (libsource (lib "eagle-import") (part "RES_10K"))
    )
    (comp (ref "R84")
      (value "10K")
      (footprint "eagle-import:RC0603N")
      (libsource (lib "eagle-import") (part "RES_10K"))
    )
    (comp (ref "F1")
      (value "2Mb (256K x 8)")
      (footprint "eagle-import:FRAM_MB85RS2MTA_FPT-8P-M09")
      (libsource (lib "eagle-import") (part "FRAM_MB85RS2MTA"))
    )
    (comp (ref "F2")
      (value "2Mb (256K x 8)")
      (footprint "eagle-import:FRAM_MB85RS2MTA_FPT-8P-M09")
      (libsource (lib "eagle-import") (part "FRAM_MB85RS2MTA"))
    )
    (comp (ref "F3")
      (value "2Mb (256K x 8)")
      (footprint "eagle-import:FRAM_MB85RS2MTA_FPT-8P-M09")
      (libsource (lib "eagle-import") (part "FRAM_MB85RS2MTA"))
    )
    (comp (ref "F4")
      (value "2Mb (256K x 8)")
      (footprint "eagle-import:FRAM_MB85RS2MTA_FPT-8P-M09")
      (libsource (lib "eagle-import") (part "FRAM_MB85RS2MTA"))
    )
    (comp (ref "F5")
      (value "2Mb (256K x 8)")
      (footprint "eagle-import:FRAM_MB85RS2MTA_FPT-8P-M09")
      (libsource (lib "eagle-import") (part "FRAM_MB85RS2MTA"))
    )
    (comp (ref "F6")
      (value "2Mb (256K x 8)")
      (footprint "eagle-import:FRAM_MB85RS2MTA_FPT-8P-M09")
      (libsource (lib "eagle-import") (part "FRAM_MB85RS2MTA"))
    )
    (comp (ref "R67")
      (value "10K")
      (footprint "eagle-import:RC0603N")
      (libsource (lib "eagle-import") (part "RES_10K"))
    )
    (comp (ref "R68")
      (value "10K")
      (footprint "eagle-import:RC0603N")
      (libsource (lib "eagle-import") (part "RES_10K"))
    )
    (comp (ref "R69")
      (value "10K")
      (footprint "eagle-import:RC0603N")
      (libsource (lib "eagle-import") (part "RES_10K"))
    )
    (comp (ref "R70")
      (value "10K")
      (footprint "eagle-import:RC0603N")
      (libsource (lib "eagle-import") (part "RES_10K"))
    )
    (comp (ref "R71")
      (value "10K")
      (footprint "eagle-import:RC0603N")
      (libsource (lib "eagle-import") (part "RES_10K"))
    )
    (comp (ref "R72")
      (value "10K")
      (footprint "eagle-import:RC0603N")
      (libsource (lib "eagle-import") (part "RES_10K"))
    )
    (comp (ref "C3")
      (value "10uF")
      (footprint "eagle-import:CAP_GRM219R61A106KE44D")
      (libsource (lib "eagle-import") (part "CAP_10UF"))
    )
    (comp (ref "C4")
      (value "10uF")
      (footprint "eagle-import:CAP_GRM219R61A106KE44D")
      (libsource (lib "eagle-import") (part "CAP_10UF"))
    )
    (comp (ref "H1")
      (value "MOUNT-PAD-SQUARE3.2")
      (footprint "eagle-import:3,2-PAD-SQUARE")
      (libsource (lib "eagle-import") (part "MOUNT-PAD-SQUARE3.2"))
    )
    (comp (ref "H2")
      (value "MOUNT-PAD-SQUARE3.2")
      (footprint "eagle-import:3,2-PAD-SQUARE")
      (libsource (lib "eagle-import") (part "MOUNT-PAD-SQUARE3.2"))
    )
    (comp (ref "H3")
      (value "MOUNT-PAD-SQUARE3.2")
      (footprint "eagle-import:3,2-PAD-SQUARE")
      (libsource (lib "eagle-import") (part "MOUNT-PAD-SQUARE3.2"))
    )
    (comp (ref "H4")
      (value "MOUNT-PAD-SQUARE3.2")
      (footprint "eagle-import:3,2-PAD-SQUARE")
      (libsource (lib "eagle-import") (part "MOUNT-PAD-SQUARE3.2"))
    )
    (comp (ref "J$1")
      (value "FRAM_A")
      (footprint "eagle-import:WIREWRAPPOST")
      (libsource (lib "eagle-import") (part "WIREPOST"))
    )
    (comp (ref "J$2")
      (value "FRAM_A")
      (footprint "eagle-import:WIREWRAPPOST")
      (libsource (lib "eagle-import") (part "WIREPOST"))
    )
    (comp (ref "J$3")
      (value "FRAM_A")
      (footprint "eagle-import:WIREWRAPPOST")
      (libsource (lib "eagle-import") (part "WIREPOST"))
    )
    (comp (ref "J$4")
      (value "FRAM_A")
      (footprint "eagle-import:WIREWRAPPOST")
      (libsource (lib "eagle-import") (part "WIREPOST"))
    )
    (comp (ref "U1")
      (value "DS18B20U+T&R")
      (footprint "eagle-import:SOP65P500X110-8N")
      (fields (field (name "MF") "Maxim Integrated") (field (name "MP") "DS18B20U+T&amp;R"))
      (libsource (lib "eagle-import") (part "DS18B20U+T&R"))
    )
    (comp (ref "U2")
      (value "MIC5225")
      (footprint "eagle-import:SOT23-5")
      (libsource (lib "eagle-import") (part "MIC5225"))
    )
    (comp (ref "U3")
      (value "DS18B20U+T&R")
      (footprint "eagle-import:SOP65P500X110-8N")
      (fields (field (name "MF") "Maxim Integrated") (field (name "MP") "DS18B20U+T&amp;R"))
      (libsource (lib "eagle-import") (part "DS18B20U+T&R"))
    )
    (comp (ref "U4")
      (value "DS18B20U+T&R")
      (footprint "eagle-import:SOP65P500X110-8N")
      (fields (field (name "MF") "Maxim Integrated") (field (name "MP") "DS18B20U+T&amp;R"))
      (libsource (lib "eagle-import") (part "DS18B20U+T&R"))
    )
    (comp (ref "F7")
      (value "2Mb (256K x 8)")
      (footprint "eagle-import:FRAM_MB85RS2MTA_FPT-8P-M09")
      (libsource (lib "eagle-import") (part "FRAM_MB85RS2MTA"))
    )
    (comp (ref "F8")
      (value "2Mb (256K x 8)")
      (footprint "eagle-import:FRAM_MB85RS2MTA_FPT-8P-M09")
      (libsource (lib "eagle-import") (part "FRAM_MB85RS2MTA"))
    )
    (comp (ref "F9")
      (value "2Mb (256K x 8)")
      (footprint "eagle-import:FRAM_MB85RS2MTA_FPT-8P-M09")
      (libsource (lib "eagle-import") (part "FRAM_MB85RS2MTA"))
    )
    (comp (ref "F10")
      (value "2Mb (256K x 8)")
      (footprint "eagle-import:FRAM_MB85RS2MTA_FPT-8P-M09")
      (libsource (lib "eagle-import") (part "FRAM_MB85RS2MTA"))
    )
    (comp (ref "F11")
      (value "2Mb (256K x 8)")
      (footprint "eagle-import:FRAM_MB85RS2MTA_FPT-8P-M09")
      (libsource (lib "eagle-import") (part "FRAM_MB85RS2MTA"))
    )
    (comp (ref "F12")
      (value "2Mb (256K x 8)")
      (footprint "eagle-import:FRAM_MB85RS2MTA_FPT-8P-M09")
      (libsource (lib "eagle-import") (part "FRAM_MB85RS2MTA"))
    )
    (comp (ref "R73")
      (value "10K")
      (footprint "eagle-import:RC0603N")
      (libsource (lib "eagle-import") (part "RES_10K"))
    )
    (comp (ref "R74")
      (value "10K")
      (footprint "eagle-import:RC0603N")
      (libsource (lib "eagle-import") (part "RES_10K"))
    )
    (comp (ref "R75")
      (value "10K")
      (footprint "eagle-import:RC0603N")
      (libsource (lib "eagle-import") (part "RES_10K"))
    )
    (comp (ref "R76")
      (value "10K")
      (footprint "eagle-import:RC0603N")
      (libsource (lib "eagle-import") (part "RES_10K"))
    )
    (comp (ref "R77")
      (value "10K")
      (footprint "eagle-import:RC0603N")
      (libsource (lib "eagle-import") (part "RES_10K"))
    )
    (comp (ref "R78")
      (value "10K")
      (footprint "eagle-import:RC0603N")
      (libsource (lib "eagle-import") (part "RES_10K"))
    )
    (comp (ref "F25")
      (value "2Mb (256K x 8)")
      (footprint "eagle-import:FRAM_MB85RS2MTA_FPT-8P-M09")
      (libsource (lib "eagle-import") (part "FRAM_MB85RS2MTA"))
    )
    (comp (ref "F26")
      (value "2Mb (256K x 8)")
      (footprint "eagle-import:FRAM_MB85RS2MTA_FPT-8P-M09")
      (libsource (lib "eagle-import") (part "FRAM_MB85RS2MTA"))
    )
    (comp (ref "F27")
      (value "2Mb (256K x 8)")
      (footprint "eagle-import:FRAM_MB85RS2MTA_FPT-8P-M09")
      (libsource (lib "eagle-import") (part "FRAM_MB85RS2MTA"))
    )
    (comp (ref "F28")
      (value "2Mb (256K x 8)")
      (footprint "eagle-import:FRAM_MB85RS2MTA_FPT-8P-M09")
      (libsource (lib "eagle-import") (part "FRAM_MB85RS2MTA"))
    )
    (comp (ref "F29")
      (value "2Mb (256K x 8)")
      (footprint "eagle-import:FRAM_MB85RS2MTA_FPT-8P-M09")
      (libsource (lib "eagle-import") (part "FRAM_MB85RS2MTA"))
    )
    (comp (ref "F30")
      (value "2Mb (256K x 8)")
      (footprint "eagle-import:FRAM_MB85RS2MTA_FPT-8P-M09")
      (libsource (lib "eagle-import") (part "FRAM_MB85RS2MTA"))
    )
    (comp (ref "R91")
      (value "10K")
      (footprint "eagle-import:RC0603N")
      (libsource (lib "eagle-import") (part "RES_10K"))
    )
    (comp (ref "R92")
      (value "10K")
      (footprint "eagle-import:RC0603N")
      (libsource (lib "eagle-import") (part "RES_10K"))
    )
    (comp (ref "R93")
      (value "10K")
      (footprint "eagle-import:RC0603N")
      (libsource (lib "eagle-import") (part "RES_10K"))
    )
    (comp (ref "R94")
      (value "10K")
      (footprint "eagle-import:RC0603N")
      (libsource (lib "eagle-import") (part "RES_10K"))
    )
    (comp (ref "R95")
      (value "10K")
      (footprint "eagle-import:RC0603N")
      (libsource (lib "eagle-import") (part "RES_10K"))
    )
    (comp (ref "R96")
      (value "10K")
      (footprint "eagle-import:RC0603N")
      (libsource (lib "eagle-import") (part "RES_10K"))
    )
  )
  (nets
    (net (code "1") (name "3.3V") (class "Default")
      (node (ref "C4") (pin "2") (pinfunction "2_2") (pintype "passive"))
      (node (ref "F1") (pin "8") (pinfunction "VDD_8") (pintype "passive"))
      (node (ref "F10") (pin "8") (pinfunction "VDD_8") (pintype "passive"))
      (node (ref "F11") (pin "8") (pinfunction "VDD_8") (pintype "passive"))
      (node (ref "F12") (pin "8") (pinfunction "VDD_8") (pintype "passive"))
      (node (ref "F13") (pin "8") (pinfunction "VDD_8") (pintype "passive"))
      (node (ref "F14") (pin "8") (pinfunction "VDD_8") (pintype "passive"))
      (node (ref "F15") (pin "8") (pinfunction "VDD_8") (pintype "passive"))
      (node (ref "F16") (pin "8") (pinfunction "VDD_8") (pintype "passive"))
      (node (ref "F17") (pin "8") (pinfunction "VDD_8") (pintype "passive"))
      (node (ref "F18") (pin "8") (pinfunction "VDD_8") (pintype "passive"))
      (node (ref "F19") (pin "8") (pinfunction "VDD_8") (pintype "passive"))
      (node (ref "F2") (pin "8") (pinfunction "VDD_8") (pintype "passive"))
      (node (ref "F20") (pin "8") (pinfunction "VDD_8") (pintype "passive"))
      (node (ref "F21") (pin "8") (pinfunction "VDD_8") (pintype "passive"))
      (node (ref "F22") (pin "8") (pinfunction "VDD_8") (pintype "passive"))
      (node (ref "F23") (pin "8") (pinfunction "VDD_8") (pintype "passive"))
      (node (ref "F24") (pin "8") (pinfunction "VDD_8") (pintype "passive"))
      (node (ref "F25") (pin "8") (pinfunction "VDD_8") (pintype "passive"))
      (node (ref "F26") (pin "8") (pinfunction "VDD_8") (pintype "passive"))
      (node (ref "F27") (pin "8") (pinfunction "VDD_8") (pintype "passive"))
      (node (ref "F28") (pin "8") (pinfunction "VDD_8") (pintype "passive"))
      (node (ref "F29") (pin "8") (pinfunction "VDD_8") (pintype "passive"))
      (node (ref "F3") (pin "8") (pinfunction "VDD_8") (pintype "passive"))
      (node (ref "F30") (pin "8") (pinfunction "VDD_8") (pintype "passive"))
      (node (ref "F4") (pin "8") (pinfunction "VDD_8") (pintype "passive"))
      (node (ref "F5") (pin "8") (pinfunction "VDD_8") (pintype "passive"))
      (node (ref "F6") (pin "8") (pinfunction "VDD_8") (pintype "passive"))
      (node (ref "F7") (pin "8") (pinfunction "VDD_8") (pintype "passive"))
      (node (ref "F8") (pin "8") (pinfunction "VDD_8") (pintype "passive"))
      (node (ref "F9") (pin "8") (pinfunction "VDD_8") (pintype "passive"))
      (node (ref "Q1") (pin "1") (pinfunction "G_1") (pintype "bidirectional"))
      (node (ref "Q10") (pin "1") (pinfunction "G_1") (pintype "bidirectional"))
      (node (ref "Q11") (pin "1") (pinfunction "G_1") (pintype "bidirectional"))
      (node (ref "Q12") (pin "1") (pinfunction "G_1") (pintype "bidirectional"))
      (node (ref "Q13") (pin "1") (pinfunction "G_1") (pintype "bidirectional"))
      (node (ref "Q14") (pin "1") (pinfunction "G_1") (pintype "bidirectional"))
      (node (ref "Q15") (pin "1") (pinfunction "G_1") (pintype "bidirectional"))
      (node (ref "Q16") (pin "1") (pinfunction "G_1") (pintype "bidirectional"))
      (node (ref "Q17") (pin "1") (pinfunction "G_1") (pintype "bidirectional"))
      (node (ref "Q18") (pin "1") (pinfunction "G_1") (pintype "bidirectional"))
      (node (ref "Q19") (pin "1") (pinfunction "G_1") (pintype "bidirectional"))
      (node (ref "Q2") (pin "1") (pinfunction "G_1") (pintype "bidirectional"))
      (node (ref "Q20") (pin "1") (pinfunction "G_1") (pintype "bidirectional"))
      (node (ref "Q21") (pin "1") (pinfunction "G_1") (pintype "bidirectional"))
      (node (ref "Q22") (pin "1") (pinfunction "G_1") (pintype "bidirectional"))
      (node (ref "Q23") (pin "1") (pinfunction "G_1") (pintype "bidirectional"))
      (node (ref "Q24") (pin "1") (pinfunction "G_1") (pintype "bidirectional"))
      (node (ref "Q25") (pin "1") (pinfunction "G_1") (pintype "bidirectional"))
      (node (ref "Q26") (pin "1") (pinfunction "G_1") (pintype "bidirectional"))
      (node (ref "Q27") (pin "1") (pinfunction "G_1") (pintype "bidirectional"))
      (node (ref "Q28") (pin "1") (pinfunction "G_1") (pintype "bidirectional"))
      (node (ref "Q29") (pin "1") (pinfunction "G_1") (pintype "bidirectional"))
      (node (ref "Q3") (pin "1") (pinfunction "G_1") (pintype "bidirectional"))
      (node (ref "Q30") (pin "1") (pinfunction "G_1") (pintype "bidirectional"))
      (node (ref "Q31") (pin "1") (pinfunction "G_1") (pintype "bidirectional"))
      (node (ref "Q32") (pin "1") (pinfunction "G_1") (pintype "bidirectional"))
      (node (ref "Q33") (pin "1") (pinfunction "G_1") (pintype "bidirectional"))
      (node (ref "Q4") (pin "1") (pinfunction "G_1") (pintype "bidirectional"))
      (node (ref "Q5") (pin "1") (pinfunction "G_1") (pintype "bidirectional"))
      (node (ref "Q6") (pin "1") (pinfunction "G_1") (pintype "bidirectional"))
      (node (ref "Q7") (pin "1") (pinfunction "G_1") (pintype "bidirectional"))
      (node (ref "Q8") (pin "1") (pinfunction "G_1") (pintype "bidirectional"))
      (node (ref "Q9") (pin "1") (pinfunction "G_1") (pintype "bidirectional"))
      (node (ref "R1") (pin "1") (pinfunction "11_1") (pintype "passive"))
      (node (ref "R10") (pin "1") (pinfunction "11_1") (pintype "passive"))
      (node (ref "R11") (pin "1") (pinfunction "11_1") (pintype "passive"))
      (node (ref "R12") (pin "1") (pinfunction "11_1") (pintype "passive"))
      (node (ref "R17") (pin "1") (pinfunction "11_1") (pintype "passive"))
      (node (ref "R18") (pin "1") (pinfunction "11_1") (pintype "passive"))
      (node (ref "R19") (pin "1") (pinfunction "11_1") (pintype "passive"))
      (node (ref "R2") (pin "1") (pinfunction "11_1") (pintype "passive"))
      (node (ref "R20") (pin "1") (pinfunction "11_1") (pintype "passive"))
      (node (ref "R25") (pin "1") (pinfunction "11_1") (pintype "passive"))
      (node (ref "R26") (pin "1") (pinfunction "11_1") (pintype "passive"))
      (node (ref "R29") (pin "1") (pinfunction "11_1") (pintype "passive"))
      (node (ref "R3") (pin "1") (pinfunction "11_1") (pintype "passive"))
      (node (ref "R30") (pin "1") (pinfunction "11_1") (pintype "passive"))
      (node (ref "R31") (pin "1") (pinfunction "11_1") (pintype "passive"))
      (node (ref "R32") (pin "1") (pinfunction "11_1") (pintype "passive"))
      (node (ref "R37") (pin "1") (pinfunction "11_1") (pintype "passive"))
      (node (ref "R38") (pin "1") (pinfunction "11_1") (pintype "passive"))
      (node (ref "R39") (pin "1") (pinfunction "11_1") (pintype "passive"))
      (node (ref "R4") (pin "1") (pinfunction "11_1") (pintype "passive"))
      (node (ref "R40") (pin "1") (pinfunction "11_1") (pintype "passive"))
      (node (ref "R45") (pin "1") (pinfunction "11_1") (pintype "passive"))
      (node (ref "R46") (pin "1") (pinfunction "11_1") (pintype "passive"))
      (node (ref "R47") (pin "1") (pinfunction "11_1") (pintype "passive"))
      (node (ref "R48") (pin "1") (pinfunction "11_1") (pintype "passive"))
      (node (ref "R53") (pin "1") (pinfunction "11_1") (pintype "passive"))
      (node (ref "R54") (pin "1") (pinfunction "11_1") (pintype "passive"))
      (node (ref "R55") (pin "1") (pinfunction "11_1") (pintype "passive"))
      (node (ref "R56") (pin "1") (pinfunction "11_1") (pintype "passive"))
      (node (ref "R61") (pin "1") (pinfunction "11_1") (pintype "passive"))
      (node (ref "R63") (pin "1") (pinfunction "11_1") (pintype "passive"))
      (node (ref "R65") (pin "1") (pinfunction "11_1") (pintype "passive"))
      (node (ref "R67") (pin "1") (pinfunction "11_1") (pintype "passive"))
      (node (ref "R68") (pin "1") (pinfunction "11_1") (pintype "passive"))
      (node (ref "R69") (pin "1") (pinfunction "11_1") (pintype "passive"))
      (node (ref "R70") (pin "1") (pinfunction "11_1") (pintype "passive"))
      (node (ref "R71") (pin "1") (pinfunction "11_1") (pintype "passive"))
      (node (ref "R72") (pin "1") (pinfunction "11_1") (pintype "passive"))
      (node (ref "R73") (pin "1") (pinfunction "11_1") (pintype "passive"))
      (node (ref "R74") (pin "1") (pinfunction "11_1") (pintype "passive"))
      (node (ref "R75") (pin "1") (pinfunction "11_1") (pintype "passive"))
      (node (ref "R76") (pin "1") (pinfunction "11_1") (pintype "passive"))
      (node (ref "R77") (pin "1") (pinfunction "11_1") (pintype "passive"))
      (node (ref "R78") (pin "1") (pinfunction "11_1") (pintype "passive"))
      (node (ref "R79") (pin "1") (pinfunction "11_1") (pintype "passive"))
      (node (ref "R80") (pin "1") (pinfunction "11_1") (pintype "passive"))
      (node (ref "R81") (pin "1") (pinfunction "11_1") (pintype "passive"))
      (node (ref "R82") (pin "1") (pinfunction "11_1") (pintype "passive"))
      (node (ref "R83") (pin "1") (pinfunction "11_1") (pintype "passive"))
      (node (ref "R84") (pin "1") (pinfunction "11_1") (pintype "passive"))
      (node (ref "R85") (pin "1") (pinfunction "11_1") (pintype "passive"))
      (node (ref "R86") (pin "1") (pinfunction "11_1") (pintype "passive"))
      (node (ref "R87") (pin "1") (pinfunction "11_1") (pintype "passive"))
      (node (ref "R88") (pin "1") (pinfunction "11_1") (pintype "passive"))
      (node (ref "R89") (pin "1") (pinfunction "11_1") (pintype "passive"))
      (node (ref "R9") (pin "1") (pinfunction "11_1") (pintype "passive"))
      (node (ref "R90") (pin "1") (pinfunction "11_1") (pintype "passive"))
      (node (ref "R91") (pin "1") (pinfunction "11_1") (pintype "passive"))
      (node (ref "R92") (pin "1") (pinfunction "11_1") (pintype "passive"))
      (node (ref "R93") (pin "1") (pinfunction "11_1") (pintype "passive"))
      (node (ref "R94") (pin "1") (pinfunction "11_1") (pintype "passive"))
      (node (ref "R95") (pin "1") (pinfunction "11_1") (pintype "passive"))
      (node (ref "R96") (pin "1") (pinfunction "11_1") (pintype "passive"))
      (node (ref "U2") (pin "OUT") (pinfunction "OUT_OUT") (pintype "bidirectional"))
    )
    (net (code "2") (name "5V") (class "Default")
      (node (ref "C3") (pin "2") (pinfunction "2_2") (pintype "passive"))
      (node (ref "J$1") (pin "12") (pinfunction "12_12") (pintype "passive"))
      (node (ref "J$4") (pin "3") (pinfunction "3_3") (pintype "passive"))
      (node (ref "R13") (pin "1") (pinfunction "11_1") (pintype "passive"))
      (node (ref "R14") (pin "1") (pinfunction "11_1") (pintype "passive"))
      (node (ref "R15") (pin "1") (pinfunction "11_1") (pintype "passive"))
      (node (ref "R16") (pin "1") (pinfunction "11_1") (pintype "passive"))
      (node (ref "R21") (pin "1") (pinfunction "11_1") (pintype "passive"))
      (node (ref "R22") (pin "1") (pinfunction "11_1") (pintype "passive"))
      (node (ref "R23") (pin "1") (pinfunction "11_1") (pintype "passive"))
      (node (ref "R24") (pin "1") (pinfunction "11_1") (pintype "passive"))
      (node (ref "R27") (pin "1") (pinfunction "11_1") (pintype "passive"))
      (node (ref "R28") (pin "1") (pinfunction "11_1") (pintype "passive"))
      (node (ref "R33") (pin "1") (pinfunction "11_1") (pintype "passive"))
      (node (ref "R34") (pin "1") (pinfunction "11_1") (pintype "passive"))
      (node (ref "R35") (pin "1") (pinfunction "11_1") (pintype "passive"))
      (node (ref "R36") (pin "1") (pinfunction "11_1") (pintype "passive"))
      (node (ref "R41") (pin "1") (pinfunction "11_1") (pintype "passive"))
      (node (ref "R42") (pin "1") (pinfunction "11_1") (pintype "passive"))
      (node (ref "R43") (pin "1") (pinfunction "11_1") (pintype "passive"))
      (node (ref "R44") (pin "1") (pinfunction "11_1") (pintype "passive"))
      (node (ref "R49") (pin "1") (pinfunction "11_1") (pintype "passive"))
      (node (ref "R5") (pin "1") (pinfunction "11_1") (pintype "passive"))
      (node (ref "R50") (pin "1") (pinfunction "11_1") (pintype "passive"))
      (node (ref "R51") (pin "1") (pinfunction "11_1") (pintype "passive"))
      (node (ref "R52") (pin "1") (pinfunction "11_1") (pintype "passive"))
      (node (ref "R57") (pin "1") (pinfunction "11_1") (pintype "passive"))
      (node (ref "R58") (pin "1") (pinfunction "11_1") (pintype "passive"))
      (node (ref "R59") (pin "1") (pinfunction "11_1") (pintype "passive"))
      (node (ref "R6") (pin "1") (pinfunction "11_1") (pintype "passive"))
      (node (ref "R60") (pin "1") (pinfunction "11_1") (pintype "passive"))
      (node (ref "R62") (pin "1") (pinfunction "11_1") (pintype "passive"))
      (node (ref "R64") (pin "1") (pinfunction "11_1") (pintype "passive"))
      (node (ref "R66") (pin "1") (pinfunction "11_1") (pintype "passive"))
      (node (ref "R7") (pin "1") (pinfunction "11_1") (pintype "passive"))
      (node (ref "R8") (pin "1") (pinfunction "11_1") (pintype "passive"))
      (node (ref "U1") (pin "8") (pinfunction "VDD_8") (pintype "power_in"))
      (node (ref "U2") (pin "EN") (pinfunction "EN_EN") (pintype "bidirectional"))
      (node (ref "U2") (pin "IN") (pinfunction "IN_IN") (pintype "bidirectional"))
      (node (ref "U3") (pin "8") (pinfunction "VDD_8") (pintype "power_in"))
      (node (ref "U4") (pin "8") (pinfunction "VDD_8") (pintype "power_in"))
    )
    (net (code "3") (name "CS1") (class "Default")
      (node (ref "J$1") (pin "5") (pinfunction "5_5") (pintype "passive"))
      (node (ref "Q4") (pin "3") (pinfunction "D_3") (pintype "bidirectional"))
      (node (ref "R8") (pin "2") (pinfunction "22_2") (pintype "passive"))
    )
    (net (code "4") (name "CS1_3V") (class "Default")
      (node (ref "F1") (pin "1") (pinfunction "~{CS}_1") (pintype "passive"))
      (node (ref "Q4") (pin "2") (pinfunction "S_2") (pintype "bidirectional"))
      (node (ref "R4") (pin "2") (pinfunction "22_2") (pintype "passive"))
    )
    (net (code "5") (name "CS2") (class "Default")
      (node (ref "J$1") (pin "4") (pinfunction "4_4") (pintype "passive"))
      (node (ref "Q5") (pin "3") (pinfunction "D_3") (pintype "bidirectional"))
      (node (ref "R13") (pin "2") (pinfunction "22_2") (pintype "passive"))
    )
    (net (code "6") (name "CS2_3V") (class "Default")
      (node (ref "F2") (pin "1") (pinfunction "~{CS}_1") (pintype "passive"))
      (node (ref "Q5") (pin "2") (pinfunction "S_2") (pintype "bidirectional"))
      (node (ref "R9") (pin "2") (pinfunction "22_2") (pintype "passive"))
    )
    (net (code "7") (name "CS3") (class "Default")
      (node (ref "J$1") (pin "3") (pinfunction "3_3") (pintype "passive"))
      (node (ref "Q6") (pin "3") (pinfunction "D_3") (pintype "bidirectional"))
      (node (ref "R14") (pin "2") (pinfunction "22_2") (pintype "passive"))
    )
    (net (code "8") (name "CS3_3V") (class "Default")
      (node (ref "F3") (pin "1") (pinfunction "~{CS}_1") (pintype "passive"))
      (node (ref "Q6") (pin "2") (pinfunction "S_2") (pintype "bidirectional"))
      (node (ref "R10") (pin "2") (pinfunction "22_2") (pintype "passive"))
    )
    (net (code "9") (name "CS4") (class "Default")
      (node (ref "J$1") (pin "2") (pinfunction "2_2") (pintype "passive"))
      (node (ref "Q7") (pin "3") (pinfunction "D_3") (pintype "bidirectional"))
      (node (ref "R15") (pin "2") (pinfunction "22_2") (pintype "passive"))
    )
    (net (code "10") (name "CS4_3V") (class "Default")
      (node (ref "F4") (pin "1") (pinfunction "~{CS}_1") (pintype "passive"))
      (node (ref "Q7") (pin "2") (pinfunction "S_2") (pintype "bidirectional"))
      (node (ref "R11") (pin "2") (pinfunction "22_2") (pintype "passive"))
    )
    (net (code "11") (name "CS5") (class "Default")
      (node (ref "J$1") (pin "1") (pinfunction "1_1") (pintype "passive"))
      (node (ref "Q8") (pin "3") (pinfunction "D_3") (pintype "bidirectional"))
      (node (ref "R16") (pin "2") (pinfunction "22_2") (pintype "passive"))
    )
    (net (code "12") (name "CS5_3V") (class "Default")
      (node (ref "F5") (pin "1") (pinfunction "~{CS}_1") (pintype "passive"))
      (node (ref "Q8") (pin "2") (pinfunction "S_2") (pintype "bidirectional"))
      (node (ref "R12") (pin "2") (pinfunction "22_2") (pintype "passive"))
    )
    (net (code "13") (name "CS6") (class "Default")
      (node (ref "J$2") (pin "12") (pinfunction "12_12") (pintype "passive"))
      (node (ref "Q9") (pin "3") (pinfunction "D_3") (pintype "bidirectional"))
      (node (ref "R21") (pin "2") (pinfunction "22_2") (pintype "passive"))
    )
    (net (code "14") (name "CS6_3V") (class "Default")
      (node (ref "F6") (pin "1") (pinfunction "~{CS}_1") (pintype "passive"))
      (node (ref "Q9") (pin "2") (pinfunction "S_2") (pintype "bidirectional"))
      (node (ref "R17") (pin "2") (pinfunction "22_2") (pintype "passive"))
    )
    (net (code "15") (name "CS7") (class "Default")
      (node (ref "J$2") (pin "11") (pinfunction "11_11") (pintype "passive"))
      (node (ref "Q10") (pin "3") (pinfunction "D_3") (pintype "bidirectional"))
      (node (ref "R22") (pin "2") (pinfunction "22_2") (pintype "passive"))
    )
    (net (code "16") (name "CS7_3V") (class "Default")
      (node (ref "F7") (pin "1") (pinfunction "~{CS}_1") (pintype "passive"))
      (node (ref "Q10") (pin "2") (pinfunction "S_2") (pintype "bidirectional"))
      (node (ref "R18") (pin "2") (pinfunction "22_2") (pintype "passive"))
    )
    (net (code "17") (name "CS8") (class "Default")
      (node (ref "J$2") (pin "10") (pinfunction "10_10") (pintype "passive"))
      (node (ref "Q11") (pin "3") (pinfunction "D_3") (pintype "bidirectional"))
      (node (ref "R23") (pin "2") (pinfunction "22_2") (pintype "passive"))
    )
    (net (code "18") (name "CS8_3V") (class "Default")
      (node (ref "F8") (pin "1") (pinfunction "~{CS}_1") (pintype "passive"))
      (node (ref "Q11") (pin "2") (pinfunction "S_2") (pintype "bidirectional"))
      (node (ref "R19") (pin "2") (pinfunction "22_2") (pintype "passive"))
    )
    (net (code "19") (name "CS9") (class "Default")
      (node (ref "J$2") (pin "9") (pinfunction "9_9") (pintype "passive"))
      (node (ref "Q12") (pin "3") (pinfunction "D_3") (pintype "bidirectional"))
      (node (ref "R24") (pin "2") (pinfunction "22_2") (pintype "passive"))
    )
    (net (code "20") (name "CS9_3V") (class "Default")
      (node (ref "F9") (pin "1") (pinfunction "~{CS}_1") (pintype "passive"))
      (node (ref "Q12") (pin "2") (pinfunction "S_2") (pintype "bidirectional"))
      (node (ref "R20") (pin "2") (pinfunction "22_2") (pintype "passive"))
    )
    (net (code "21") (name "CS10") (class "Default")
      (node (ref "J$2") (pin "8") (pinfunction "8_8") (pintype "passive"))
      (node (ref "Q13") (pin "3") (pinfunction "D_3") (pintype "bidirectional"))
      (node (ref "R27") (pin "2") (pinfunction "22_2") (pintype "passive"))
    )
    (net (code "22") (name "CS10_3V") (class "Default")
      (node (ref "F10") (pin "1") (pinfunction "~{CS}_1") (pintype "passive"))
      (node (ref "Q13") (pin "2") (pinfunction "S_2") (pintype "bidirectional"))
      (node (ref "R25") (pin "2") (pinfunction "22_2") (pintype "passive"))
    )
    (net (code "23") (name "CS11") (class "Default")
      (node (ref "J$2") (pin "7") (pinfunction "7_7") (pintype "passive"))
      (node (ref "Q14") (pin "3") (pinfunction "D_3") (pintype "bidirectional"))
      (node (ref "R28") (pin "2") (pinfunction "22_2") (pintype "passive"))
    )
    (net (code "24") (name "CS11_3V") (class "Default")
      (node (ref "F11") (pin "1") (pinfunction "~{CS}_1") (pintype "passive"))
      (node (ref "Q14") (pin "2") (pinfunction "S_2") (pintype "bidirectional"))
      (node (ref "R26") (pin "2") (pinfunction "22_2") (pintype "passive"))
    )
    (net (code "25") (name "CS12") (class "Default")
      (node (ref "J$2") (pin "6") (pinfunction "6_6") (pintype "passive"))
      (node (ref "Q15") (pin "3") (pinfunction "D_3") (pintype "bidirectional"))
      (node (ref "R33") (pin "2") (pinfunction "22_2") (pintype "passive"))
    )
    (net (code "26") (name "CS12_3V") (class "Default")
      (node (ref "F12") (pin "1") (pinfunction "~{CS}_1") (pintype "passive"))
      (node (ref "Q15") (pin "2") (pinfunction "S_2") (pintype "bidirectional"))
      (node (ref "R29") (pin "2") (pinfunction "22_2") (pintype "passive"))
    )
    (net (code "27") (name "CS13") (class "Default")
      (node (ref "J$2") (pin "5") (pinfunction "5_5") (pintype "passive"))
      (node (ref "Q16") (pin "3") (pinfunction "D_3") (pintype "bidirectional"))
      (node (ref "R34") (pin "2") (pinfunction "22_2") (pintype "passive"))
    )
    (net (code "28") (name "CS13_3V") (class "Default")
      (node (ref "F13") (pin "1") (pinfunction "~{CS}_1") (pintype "passive"))
      (node (ref "Q16") (pin "2") (pinfunction "S_2") (pintype "bidirectional"))
      (node (ref "R30") (pin "2") (pinfunction "22_2") (pintype "passive"))
    )
    (net (code "29") (name "CS14") (class "Default")
      (node (ref "J$2") (pin "4") (pinfunction "4_4") (pintype "passive"))
      (node (ref "Q17") (pin "3") (pinfunction "D_3") (pintype "bidirectional"))
      (node (ref "R35") (pin "2") (pinfunction "22_2") (pintype "passive"))
    )
    (net (code "30") (name "CS14_3V") (class "Default")
      (node (ref "F14") (pin "1") (pinfunction "~{CS}_1") (pintype "passive"))
      (node (ref "Q17") (pin "2") (pinfunction "S_2") (pintype "bidirectional"))
      (node (ref "R31") (pin "2") (pinfunction "22_2") (pintype "passive"))
    )
    (net (code "31") (name "CS15") (class "Default")
      (node (ref "J$2") (pin "3") (pinfunction "3_3") (pintype "passive"))
      (node (ref "Q18") (pin "3") (pinfunction "D_3") (pintype "bidirectional"))
      (node (ref "R36") (pin "2") (pinfunction "22_2") (pintype "passive"))
    )
    (net (code "32") (name "CS15_3V") (class "Default")
      (node (ref "F15") (pin "1") (pinfunction "~{CS}_1") (pintype "passive"))
      (node (ref "Q18") (pin "2") (pinfunction "S_2") (pintype "bidirectional"))
      (node (ref "R32") (pin "2") (pinfunction "22_2") (pintype "passive"))
    )
    (net (code "33") (name "CS16") (class "Default")
      (node (ref "J$2") (pin "2") (pinfunction "2_2") (pintype "passive"))
      (node (ref "Q19") (pin "3") (pinfunction "D_3") (pintype "bidirectional"))
      (node (ref "R41") (pin "2") (pinfunction "22_2") (pintype "passive"))
    )
    (net (code "34") (name "CS16_3V") (class "Default")
      (node (ref "F16") (pin "1") (pinfunction "~{CS}_1") (pintype "passive"))
      (node (ref "Q19") (pin "2") (pinfunction "S_2") (pintype "bidirectional"))
      (node (ref "R37") (pin "2") (pinfunction "22_2") (pintype "passive"))
    )
    (net (code "35") (name "CS17") (class "Default")
      (node (ref "J$2") (pin "1") (pinfunction "1_1") (pintype "passive"))
      (node (ref "Q20") (pin "3") (pinfunction "D_3") (pintype "bidirectional"))
      (node (ref "R42") (pin "2") (pinfunction "22_2") (pintype "passive"))
    )
    (net (code "36") (name "CS17_3V") (class "Default")
      (node (ref "F17") (pin "1") (pinfunction "~{CS}_1") (pintype "passive"))
      (node (ref "Q20") (pin "2") (pinfunction "S_2") (pintype "bidirectional"))
      (node (ref "R38") (pin "2") (pinfunction "22_2") (pintype "passive"))
    )
    (net (code "37") (name "CS18") (class "Default")
      (node (ref "J$3") (pin "12") (pinfunction "12_12") (pintype "passive"))
      (node (ref "Q21") (pin "3") (pinfunction "D_3") (pintype "bidirectional"))
      (node (ref "R43") (pin "2") (pinfunction "22_2") (pintype "passive"))
    )
    (net (code "38") (name "CS18_3V") (class "Default")
      (node (ref "F18") (pin "1") (pinfunction "~{CS}_1") (pintype "passive"))
      (node (ref "Q21") (pin "2") (pinfunction "S_2") (pintype "bidirectional"))
      (node (ref "R39") (pin "2") (pinfunction "22_2") (pintype "passive"))
    )
    (net (code "39") (name "CS19") (class "Default")
      (node (ref "J$3") (pin "11") (pinfunction "11_11") (pintype "passive"))
      (node (ref "Q22") (pin "3") (pinfunction "D_3") (pintype "bidirectional"))
      (node (ref "R44") (pin "2") (pinfunction "22_2") (pintype "passive"))
    )
    (net (code "40") (name "CS19_3V") (class "Default")
      (node (ref "F19") (pin "1") (pinfunction "~{CS}_1") (pintype "passive"))
      (node (ref "Q22") (pin "2") (pinfunction "S_2") (pintype "bidirectional"))
      (node (ref "R40") (pin "2") (pinfunction "22_2") (pintype "passive"))
    )
    (net (code "41") (name "CS20") (class "Default")
      (node (ref "J$3") (pin "10") (pinfunction "10_10") (pintype "passive"))
      (node (ref "Q23") (pin "3") (pinfunction "D_3") (pintype "bidirectional"))
      (node (ref "R49") (pin "2") (pinfunction "22_2") (pintype "passive"))
    )
    (net (code "42") (name "CS20_3V") (class "Default")
      (node (ref "F20") (pin "1") (pinfunction "~{CS}_1") (pintype "passive"))
      (node (ref "Q23") (pin "2") (pinfunction "S_2") (pintype "bidirectional"))
      (node (ref "R45") (pin "2") (pinfunction "22_2") (pintype "passive"))
    )
    (net (code "43") (name "CS21") (class "Default")
      (node (ref "J$3") (pin "9") (pinfunction "9_9") (pintype "passive"))
      (node (ref "Q24") (pin "3") (pinfunction "D_3") (pintype "bidirectional"))
      (node (ref "R50") (pin "2") (pinfunction "22_2") (pintype "passive"))
    )
    (net (code "44") (name "CS21_3V") (class "Default")
      (node (ref "F21") (pin "1") (pinfunction "~{CS}_1") (pintype "passive"))
      (node (ref "Q24") (pin "2") (pinfunction "S_2") (pintype "bidirectional"))
      (node (ref "R46") (pin "2") (pinfunction "22_2") (pintype "passive"))
    )
    (net (code "45") (name "CS22") (class "Default")
      (node (ref "J$3") (pin "8") (pinfunction "8_8") (pintype "passive"))
      (node (ref "Q25") (pin "3") (pinfunction "D_3") (pintype "bidirectional"))
      (node (ref "R51") (pin "2") (pinfunction "22_2") (pintype "passive"))
    )
    (net (code "46") (name "CS22_3V") (class "Default")
      (node (ref "F22") (pin "1") (pinfunction "~{CS}_1") (pintype "passive"))
      (node (ref "Q25") (pin "2") (pinfunction "S_2") (pintype "bidirectional"))
      (node (ref "R47") (pin "2") (pinfunction "22_2") (pintype "passive"))
    )
    (net (code "47") (name "CS23") (class "Default")
      (node (ref "J$3") (pin "7") (pinfunction "7_7") (pintype "passive"))
      (node (ref "Q26") (pin "3") (pinfunction "D_3") (pintype "bidirectional"))
      (node (ref "R52") (pin "2") (pinfunction "22_2") (pintype "passive"))
    )
    (net (code "48") (name "CS23_3V") (class "Default")
      (node (ref "F23") (pin "1") (pinfunction "~{CS}_1") (pintype "passive"))
      (node (ref "Q26") (pin "2") (pinfunction "S_2") (pintype "bidirectional"))
      (node (ref "R48") (pin "2") (pinfunction "22_2") (pintype "passive"))
    )
    (net (code "49") (name "CS24") (class "Default")
      (node (ref "J$3") (pin "6") (pinfunction "6_6") (pintype "passive"))
      (node (ref "Q27") (pin "3") (pinfunction "D_3") (pintype "bidirectional"))
      (node (ref "R57") (pin "2") (pinfunction "22_2") (pintype "passive"))
    )
    (net (code "50") (name "CS24_3V") (class "Default")
      (node (ref "F24") (pin "1") (pinfunction "~{CS}_1") (pintype "passive"))
      (node (ref "Q27") (pin "2") (pinfunction "S_2") (pintype "bidirectional"))
      (node (ref "R53") (pin "2") (pinfunction "22_2") (pintype "passive"))
    )
    (net (code "51") (name "CS25") (class "Default")
      (node (ref "J$3") (pin "5") (pinfunction "5_5") (pintype "passive"))
      (node (ref "Q28") (pin "3") (pinfunction "D_3") (pintype "bidirectional"))
      (node (ref "R58") (pin "2") (pinfunction "22_2") (pintype "passive"))
    )
    (net (code "52") (name "CS25_3V") (class "Default")
      (node (ref "F25") (pin "1") (pinfunction "~{CS}_1") (pintype "passive"))
      (node (ref "Q28") (pin "2") (pinfunction "S_2") (pintype "bidirectional"))
      (node (ref "R54") (pin "2") (pinfunction "22_2") (pintype "passive"))
    )
    (net (code "53") (name "CS26") (class "Default")
      (node (ref "J$3") (pin "4") (pinfunction "4_4") (pintype "passive"))
      (node (ref "Q29") (pin "3") (pinfunction "D_3") (pintype "bidirectional"))
      (node (ref "R59") (pin "2") (pinfunction "22_2") (pintype "passive"))
    )
    (net (code "54") (name "CS26_3V") (class "Default")
      (node (ref "F26") (pin "1") (pinfunction "~{CS}_1") (pintype "passive"))
      (node (ref "Q29") (pin "2") (pinfunction "S_2") (pintype "bidirectional"))
      (node (ref "R55") (pin "2") (pinfunction "22_2") (pintype "passive"))
    )
    (net (code "55") (name "CS27") (class "Default")
      (node (ref "J$3") (pin "3") (pinfunction "3_3") (pintype "passive"))
      (node (ref "Q30") (pin "3") (pinfunction "D_3") (pintype "bidirectional"))
      (node (ref "R60") (pin "2") (pinfunction "22_2") (pintype "passive"))
    )
    (net (code "56") (name "CS27_3V") (class "Default")
      (node (ref "F27") (pin "1") (pinfunction "~{CS}_1") (pintype "passive"))
      (node (ref "Q30") (pin "2") (pinfunction "S_2") (pintype "bidirectional"))
      (node (ref "R56") (pin "2") (pinfunction "22_2") (pintype "passive"))
    )
    (net (code "57") (name "CS28") (class "Default")
      (node (ref "J$3") (pin "2") (pinfunction "2_2") (pintype "passive"))
      (node (ref "Q31") (pin "3") (pinfunction "D_3") (pintype "bidirectional"))
      (node (ref "R62") (pin "2") (pinfunction "22_2") (pintype "passive"))
    )
    (net (code "58") (name "CS28_3V") (class "Default")
      (node (ref "F28") (pin "1") (pinfunction "~{CS}_1") (pintype "passive"))
      (node (ref "Q31") (pin "2") (pinfunction "S_2") (pintype "bidirectional"))
      (node (ref "R61") (pin "2") (pinfunction "22_2") (pintype "passive"))
    )
    (net (code "59") (name "CS29") (class "Default")
      (node (ref "J$3") (pin "1") (pinfunction "1_1") (pintype "passive"))
      (node (ref "Q32") (pin "3") (pinfunction "D_3") (pintype "bidirectional"))
      (node (ref "R64") (pin "2") (pinfunction "22_2") (pintype "passive"))
    )
    (net (code "60") (name "CS29_3V") (class "Default")
      (node (ref "F29") (pin "1") (pinfunction "~{CS}_1") (pintype "passive"))
      (node (ref "Q32") (pin "2") (pinfunction "S_2") (pintype "bidirectional"))
      (node (ref "R63") (pin "2") (pinfunction "22_2") (pintype "passive"))
    )
    (net (code "61") (name "CS30") (class "Default")
      (node (ref "J$4") (pin "12") (pinfunction "12_12") (pintype "passive"))
      (node (ref "Q33") (pin "3") (pinfunction "D_3") (pintype "bidirectional"))
      (node (ref "R66") (pin "2") (pinfunction "22_2") (pintype "passive"))
    )
    (net (code "62") (name "CS30_3V") (class "Default")
      (node (ref "F30") (pin "1") (pinfunction "~{CS}_1") (pintype "passive"))
      (node (ref "Q33") (pin "2") (pinfunction "S_2") (pintype "bidirectional"))
      (node (ref "R65") (pin "2") (pinfunction "22_2") (pintype "passive"))
    )
    (net (code "63") (name "GND") (class "Default")
      (node (ref "C3") (pin "1") (pinfunction "1_1") (pintype "passive"))
      (node (ref "C4") (pin "1") (pinfunction "1_1") (pintype "passive"))
      (node (ref "F1") (pin "4") (pinfunction "VSS_4") (pintype "passive"))
      (node (ref "F10") (pin "4") (pinfunction "VSS_4") (pintype "passive"))
      (node (ref "F11") (pin "4") (pinfunction "VSS_4") (pintype "passive"))
      (node (ref "F12") (pin "4") (pinfunction "VSS_4") (pintype "passive"))
      (node (ref "F13") (pin "4") (pinfunction "VSS_4") (pintype "passive"))
      (node (ref "F14") (pin "4") (pinfunction "VSS_4") (pintype "passive"))
      (node (ref "F15") (pin "4") (pinfunction "VSS_4") (pintype "passive"))
      (node (ref "F16") (pin "4") (pinfunction "VSS_4") (pintype "passive"))
      (node (ref "F17") (pin "4") (pinfunction "VSS_4") (pintype "passive"))
      (node (ref "F18") (pin "4") (pinfunction "VSS_4") (pintype "passive"))
      (node (ref "F19") (pin "4") (pinfunction "VSS_4") (pintype "passive"))
      (node (ref "F2") (pin "4") (pinfunction "VSS_4") (pintype "passive"))
      (node (ref "F20") (pin "4") (pinfunction "VSS_4") (pintype "passive"))
      (node (ref "F21") (pin "4") (pinfunction "VSS_4") (pintype "passive"))
      (node (ref "F22") (pin "4") (pinfunction "VSS_4") (pintype "passive"))
      (node (ref "F23") (pin "4") (pinfunction "VSS_4") (pintype "passive"))
      (node (ref "F24") (pin "4") (pinfunction "VSS_4") (pintype "passive"))
      (node (ref "F25") (pin "4") (pinfunction "VSS_4") (pintype "passive"))
      (node (ref "F26") (pin "4") (pinfunction "VSS_4") (pintype "passive"))
      (node (ref "F27") (pin "4") (pinfunction "VSS_4") (pintype "passive"))
      (node (ref "F28") (pin "4") (pinfunction "VSS_4") (pintype "passive"))
      (node (ref "F29") (pin "4") (pinfunction "VSS_4") (pintype "passive"))
      (node (ref "F3") (pin "4") (pinfunction "VSS_4") (pintype "passive"))
      (node (ref "F30") (pin "4") (pinfunction "VSS_4") (pintype "passive"))
      (node (ref "F4") (pin "4") (pinfunction "VSS_4") (pintype "passive"))
      (node (ref "F5") (pin "4") (pinfunction "VSS_4") (pintype "passive"))
      (node (ref "F6") (pin "4") (pinfunction "VSS_4") (pintype "passive"))
      (node (ref "F7") (pin "4") (pinfunction "VSS_4") (pintype "passive"))
      (node (ref "F8") (pin "4") (pinfunction "VSS_4") (pintype "passive"))
      (node (ref "F9") (pin "4") (pinfunction "VSS_4") (pintype "passive"))
      (node (ref "J$1") (pin "10") (pinfunction "10_10") (pintype "passive"))
      (node (ref "J$1") (pin "11") (pinfunction "11_11") (pintype "passive"))
      (node (ref "J$1") (pin "9") (pinfunction "9_9") (pintype "passive"))
      (node (ref "J$4") (pin "1") (pinfunction "1_1") (pintype "passive"))
      (node (ref "J$4") (pin "2") (pinfunction "2_2") (pintype "passive"))
      (node (ref "U1") (pin "4") (pinfunction "GND_4") (pintype "passive"))
      (node (ref "U2") (pin "GND") (pinfunction "GND_GND") (pintype "bidirectional"))
      (node (ref "U3") (pin "4") (pinfunction "GND_4") (pintype "passive"))
      (node (ref "U4") (pin "4") (pinfunction "GND_4") (pintype "passive"))
    )
    (net (code "64") (name "MISO") (class "Default")
      (node (ref "J$1") (pin "7") (pinfunction "7_7") (pintype "passive"))
      (node (ref "Q2") (pin "3") (pinfunction "D_3") (pintype "bidirectional"))
      (node (ref "R6") (pin "2") (pinfunction "22_2") (pintype "passive"))
    )
    (net (code "65") (name "MISO_3V") (class "Default")
      (node (ref "F1") (pin "2") (pinfunction "SO_2") (pintype "passive"))
      (node (ref "F10") (pin "2") (pinfunction "SO_2") (pintype "passive"))
      (node (ref "F11") (pin "2") (pinfunction "SO_2") (pintype "passive"))
      (node (ref "F12") (pin "2") (pinfunction "SO_2") (pintype "passive"))
      (node (ref "F13") (pin "2") (pinfunction "SO_2") (pintype "passive"))
      (node (ref "F14") (pin "2") (pinfunction "SO_2") (pintype "passive"))
      (node (ref "F15") (pin "2") (pinfunction "SO_2") (pintype "passive"))
      (node (ref "F16") (pin "2") (pinfunction "SO_2") (pintype "passive"))
      (node (ref "F17") (pin "2") (pinfunction "SO_2") (pintype "passive"))
      (node (ref "F18") (pin "2") (pinfunction "SO_2") (pintype "passive"))
      (node (ref "F19") (pin "2") (pinfunction "SO_2") (pintype "passive"))
      (node (ref "F2") (pin "2") (pinfunction "SO_2") (pintype "passive"))
      (node (ref "F20") (pin "2") (pinfunction "SO_2") (pintype "passive"))
      (node (ref "F21") (pin "2") (pinfunction "SO_2") (pintype "passive"))
      (node (ref "F22") (pin "2") (pinfunction "SO_2") (pintype "passive"))
      (node (ref "F23") (pin "2") (pinfunction "SO_2") (pintype "passive"))
      (node (ref "F24") (pin "2") (pinfunction "SO_2") (pintype "passive"))
      (node (ref "F25") (pin "2") (pinfunction "SO_2") (pintype "passive"))
      (node (ref "F26") (pin "2") (pinfunction "SO_2") (pintype "passive"))
      (node (ref "F27") (pin "2") (pinfunction "SO_2") (pintype "passive"))
      (node (ref "F28") (pin "2") (pinfunction "SO_2") (pintype "passive"))
      (node (ref "F29") (pin "2") (pinfunction "SO_2") (pintype "passive"))
      (node (ref "F3") (pin "2") (pinfunction "SO_2") (pintype "passive"))
      (node (ref "F30") (pin "2") (pinfunction "SO_2") (pintype "passive"))
      (node (ref "F4") (pin "2") (pinfunction "SO_2") (pintype "passive"))
      (node (ref "F5") (pin "2") (pinfunction "SO_2") (pintype "passive"))
      (node (ref "F6") (pin "2") (pinfunction "SO_2") (pintype "passive"))
      (node (ref "F7") (pin "2") (pinfunction "SO_2") (pintype "passive"))
      (node (ref "F8") (pin "2") (pinfunction "SO_2") (pintype "passive"))
      (node (ref "F9") (pin "2") (pinfunction "SO_2") (pintype "passive"))
      (node (ref "Q2") (pin "2") (pinfunction "S_2") (pintype "bidirectional"))
      (node (ref "R2") (pin "2") (pinfunction "22_2") (pintype "passive"))
    )
    (net (code "66") (name "MOSI") (class "Default")
      (node (ref "J$1") (pin "8") (pinfunction "8_8") (pintype "passive"))
      (node (ref "Q3") (pin "3") (pinfunction "D_3") (pintype "bidirectional"))
      (node (ref "R7") (pin "2") (pinfunction "22_2") (pintype "passive"))
    )
    (net (code "67") (name "MOSI_3V") (class "Default")
      (node (ref "F1") (pin "5") (pinfunction "SI_5") (pintype "passive"))
      (node (ref "F10") (pin "5") (pinfunction "SI_5") (pintype "passive"))
      (node (ref "F11") (pin "5") (pinfunction "SI_5") (pintype "passive"))
      (node (ref "F12") (pin "5") (pinfunction "SI_5") (pintype "passive"))
      (node (ref "F13") (pin "5") (pinfunction "SI_5") (pintype "passive"))
      (node (ref "F14") (pin "5") (pinfunction "SI_5") (pintype "passive"))
      (node (ref "F15") (pin "5") (pinfunction "SI_5") (pintype "passive"))
      (node (ref "F16") (pin "5") (pinfunction "SI_5") (pintype "passive"))
      (node (ref "F17") (pin "5") (pinfunction "SI_5") (pintype "passive"))
      (node (ref "F18") (pin "5") (pinfunction "SI_5") (pintype "passive"))
      (node (ref "F19") (pin "5") (pinfunction "SI_5") (pintype "passive"))
      (node (ref "F2") (pin "5") (pinfunction "SI_5") (pintype "passive"))
      (node (ref "F20") (pin "5") (pinfunction "SI_5") (pintype "passive"))
      (node (ref "F21") (pin "5") (pinfunction "SI_5") (pintype "passive"))
      (node (ref "F22") (pin "5") (pinfunction "SI_5") (pintype "passive"))
      (node (ref "F23") (pin "5") (pinfunction "SI_5") (pintype "passive"))
      (node (ref "F24") (pin "5") (pinfunction "SI_5") (pintype "passive"))
      (node (ref "F25") (pin "5") (pinfunction "SI_5") (pintype "passive"))
      (node (ref "F26") (pin "5") (pinfunction "SI_5") (pintype "passive"))
      (node (ref "F27") (pin "5") (pinfunction "SI_5") (pintype "passive"))
      (node (ref "F28") (pin "5") (pinfunction "SI_5") (pintype "passive"))
      (node (ref "F29") (pin "5") (pinfunction "SI_5") (pintype "passive"))
      (node (ref "F3") (pin "5") (pinfunction "SI_5") (pintype "passive"))
      (node (ref "F30") (pin "5") (pinfunction "SI_5") (pintype "passive"))
      (node (ref "F4") (pin "5") (pinfunction "SI_5") (pintype "passive"))
      (node (ref "F5") (pin "5") (pinfunction "SI_5") (pintype "passive"))
      (node (ref "F6") (pin "5") (pinfunction "SI_5") (pintype "passive"))
      (node (ref "F7") (pin "5") (pinfunction "SI_5") (pintype "passive"))
      (node (ref "F8") (pin "5") (pinfunction "SI_5") (pintype "passive"))
      (node (ref "F9") (pin "5") (pinfunction "SI_5") (pintype "passive"))
      (node (ref "Q3") (pin "2") (pinfunction "S_2") (pintype "bidirectional"))
      (node (ref "R3") (pin "2") (pinfunction "22_2") (pintype "passive"))
    )
    (net (code "68") (name "Net-(F1-~{HOLD})") (class "Default")
      (node (ref "F1") (pin "7") (pinfunction "~{HOLD}_7") (pintype "passive"))
      (node (ref "R67") (pin "2") (pinfunction "22_2") (pintype "passive"))
    )
    (net (code "69") (name "Net-(F2-~{HOLD})") (class "Default")
      (node (ref "F2") (pin "7") (pinfunction "~{HOLD}_7") (pintype "passive"))
      (node (ref "R68") (pin "2") (pinfunction "22_2") (pintype "passive"))
    )
    (net (code "70") (name "Net-(F3-~{HOLD})") (class "Default")
      (node (ref "F3") (pin "7") (pinfunction "~{HOLD}_7") (pintype "passive"))
      (node (ref "R69") (pin "2") (pinfunction "22_2") (pintype "passive"))
    )
    (net (code "71") (name "Net-(F4-~{HOLD})") (class "Default")
      (node (ref "F4") (pin "7") (pinfunction "~{HOLD}_7") (pintype "passive"))
      (node (ref "R70") (pin "2") (pinfunction "22_2") (pintype "passive"))
    )
    (net (code "72") (name "Net-(F5-~{HOLD})") (class "Default")
      (node (ref "F5") (pin "7") (pinfunction "~{HOLD}_7") (pintype "passive"))
      (node (ref "R71") (pin "2") (pinfunction "22_2") (pintype "passive"))
    )
    (net (code "73") (name "Net-(F6-~{HOLD})") (class "Default")
      (node (ref "F6") (pin "7") (pinfunction "~{HOLD}_7") (pintype "passive"))
      (node (ref "R72") (pin "2") (pinfunction "22_2") (pintype "passive"))
    )
    (net (code "74") (name "Net-(F7-~{HOLD})") (class "Default")
      (node (ref "F7") (pin "7") (pinfunction "~{HOLD}_7") (pintype "passive"))
      (node (ref "R73") (pin "2") (pinfunction "22_2") (pintype "passive"))
    )
    (net (code "75") (name "Net-(F8-~{HOLD})") (class "Default")
      (node (ref "F8") (pin "7") (pinfunction "~{HOLD}_7") (pintype "passive"))
      (node (ref "R74") (pin "2") (pinfunction "22_2") (pintype "passive"))
    )
    (net (code "76") (name "Net-(F9-~{HOLD})") (class "Default")
      (node (ref "F9") (pin "7") (pinfunction "~{HOLD}_7") (pintype "passive"))
      (node (ref "R75") (pin "2") (pinfunction "22_2") (pintype "passive"))
    )
    (net (code "77") (name "Net-(F10-~{HOLD})") (class "Default")
      (node (ref "F10") (pin "7") (pinfunction "~{HOLD}_7") (pintype "passive"))
      (node (ref "R76") (pin "2") (pinfunction "22_2") (pintype "passive"))
    )
    (net (code "78") (name "Net-(F11-~{HOLD})") (class "Default")
      (node (ref "F11") (pin "7") (pinfunction "~{HOLD}_7") (pintype "passive"))
      (node (ref "R77") (pin "2") (pinfunction "22_2") (pintype "passive"))
    )
    (net (code "79") (name "Net-(F12-~{HOLD})") (class "Default")
      (node (ref "F12") (pin "7") (pinfunction "~{HOLD}_7") (pintype "passive"))
      (node (ref "R78") (pin "2") (pinfunction "22_2") (pintype "passive"))
    )
    (net (code "80") (name "Net-(F13-~{HOLD})") (class "Default")
      (node (ref "F13") (pin "7") (pinfunction "~{HOLD}_7") (pintype "passive"))
      (node (ref "R79") (pin "2") (pinfunction "22_2") (pintype "passive"))
    )
    (net (code "81") (name "Net-(F14-~{HOLD})") (class "Default")
      (node (ref "F14") (pin "7") (pinfunction "~{HOLD}_7") (pintype "passive"))
      (node (ref "R80") (pin "2") (pinfunction "22_2") (pintype "passive"))
    )
    (net (code "82") (name "Net-(F15-~{HOLD})") (class "Default")
      (node (ref "F15") (pin "7") (pinfunction "~{HOLD}_7") (pintype "passive"))
      (node (ref "R81") (pin "2") (pinfunction "22_2") (pintype "passive"))
    )
    (net (code "83") (name "Net-(F16-~{HOLD})") (class "Default")
      (node (ref "F16") (pin "7") (pinfunction "~{HOLD}_7") (pintype "passive"))
      (node (ref "R82") (pin "2") (pinfunction "22_2") (pintype "passive"))
    )
    (net (code "84") (name "Net-(F17-~{HOLD})") (class "Default")
      (node (ref "F17") (pin "7") (pinfunction "~{HOLD}_7") (pintype "passive"))
      (node (ref "R83") (pin "2") (pinfunction "22_2") (pintype "passive"))
    )
    (net (code "85") (name "Net-(F18-~{HOLD})") (class "Default")
      (node (ref "F18") (pin "7") (pinfunction "~{HOLD}_7") (pintype "passive"))
      (node (ref "R84") (pin "2") (pinfunction "22_2") (pintype "passive"))
    )
    (net (code "86") (name "Net-(F19-~{HOLD})") (class "Default")
      (node (ref "F19") (pin "7") (pinfunction "~{HOLD}_7") (pintype "passive"))
      (node (ref "R85") (pin "2") (pinfunction "22_2") (pintype "passive"))
    )
    (net (code "87") (name "Net-(F20-~{HOLD})") (class "Default")
      (node (ref "F20") (pin "7") (pinfunction "~{HOLD}_7") (pintype "passive"))
      (node (ref "R86") (pin "2") (pinfunction "22_2") (pintype "passive"))
    )
    (net (code "88") (name "Net-(F21-~{HOLD})") (class "Default")
      (node (ref "F21") (pin "7") (pinfunction "~{HOLD}_7") (pintype "passive"))
      (node (ref "R87") (pin "2") (pinfunction "22_2") (pintype "passive"))
    )
    (net (code "89") (name "Net-(F22-~{HOLD})") (class "Default")
      (node (ref "F22") (pin "7") (pinfunction "~{HOLD}_7") (pintype "passive"))
      (node (ref "R88") (pin "2") (pinfunction "22_2") (pintype "passive"))
    )
    (net (code "90") (name "Net-(F23-~{HOLD})") (class "Default")
      (node (ref "F23") (pin "7") (pinfunction "~{HOLD}_7") (pintype "passive"))
      (node (ref "R89") (pin "2") (pinfunction "22_2") (pintype "passive"))
    )
    (net (code "91") (name "Net-(F24-~{HOLD})") (class "Default")
      (node (ref "F24") (pin "7") (pinfunction "~{HOLD}_7") (pintype "passive"))
      (node (ref "R90") (pin "2") (pinfunction "22_2") (pintype "passive"))
    )
    (net (code "92") (name "Net-(F25-~{HOLD})") (class "Default")
      (node (ref "F25") (pin "7") (pinfunction "~{HOLD}_7") (pintype "passive"))
      (node (ref "R91") (pin "2") (pinfunction "22_2") (pintype "passive"))
    )
    (net (code "93") (name "Net-(F26-~{HOLD})") (class "Default")
      (node (ref "F26") (pin "7") (pinfunction "~{HOLD}_7") (pintype "passive"))
      (node (ref "R92") (pin "2") (pinfunction "22_2") (pintype "passive"))
    )
    (net (code "94") (name "Net-(F27-~{HOLD})") (class "Default")
      (node (ref "F27") (pin "7") (pinfunction "~{HOLD}_7") (pintype "passive"))
      (node (ref "R93") (pin "2") (pinfunction "22_2") (pintype "passive"))
    )
    (net (code "95") (name "Net-(F28-~{HOLD})") (class "Default")
      (node (ref "F28") (pin "7") (pinfunction "~{HOLD}_7") (pintype "passive"))
      (node (ref "R94") (pin "2") (pinfunction "22_2") (pintype "passive"))
    )
    (net (code "96") (name "Net-(F29-~{HOLD})") (class "Default")
      (node (ref "F29") (pin "7") (pinfunction "~{HOLD}_7") (pintype "passive"))
      (node (ref "R95") (pin "2") (pinfunction "22_2") (pintype "passive"))
    )
    (net (code "97") (name "Net-(F30-~{HOLD})") (class "Default")
      (node (ref "F30") (pin "7") (pinfunction "~{HOLD}_7") (pintype "passive"))
      (node (ref "R96") (pin "2") (pinfunction "22_2") (pintype "passive"))
    )
    (net (code "98") (name "SCK") (class "Default")
      (node (ref "J$1") (pin "6") (pinfunction "6_6") (pintype "passive"))
      (node (ref "Q1") (pin "3") (pinfunction "D_3") (pintype "bidirectional"))
      (node (ref "R5") (pin "2") (pinfunction "22_2") (pintype "passive"))
    )
    (net (code "99") (name "SCK_3V") (class "Default")
      (node (ref "F1") (pin "6") (pinfunction "SCK_6") (pintype "passive"))
      (node (ref "F10") (pin "6") (pinfunction "SCK_6") (pintype "passive"))
      (node (ref "F11") (pin "6") (pinfunction "SCK_6") (pintype "passive"))
      (node (ref "F12") (pin "6") (pinfunction "SCK_6") (pintype "passive"))
      (node (ref "F13") (pin "6") (pinfunction "SCK_6") (pintype "passive"))
      (node (ref "F14") (pin "6") (pinfunction "SCK_6") (pintype "passive"))
      (node (ref "F15") (pin "6") (pinfunction "SCK_6") (pintype "passive"))
      (node (ref "F16") (pin "6") (pinfunction "SCK_6") (pintype "passive"))
      (node (ref "F17") (pin "6") (pinfunction "SCK_6") (pintype "passive"))
      (node (ref "F18") (pin "6") (pinfunction "SCK_6") (pintype "passive"))
      (node (ref "F19") (pin "6") (pinfunction "SCK_6") (pintype "passive"))
      (node (ref "F2") (pin "6") (pinfunction "SCK_6") (pintype "passive"))
      (node (ref "F20") (pin "6") (pinfunction "SCK_6") (pintype "passive"))
      (node (ref "F21") (pin "6") (pinfunction "SCK_6") (pintype "passive"))
      (node (ref "F22") (pin "6") (pinfunction "SCK_6") (pintype "passive"))
      (node (ref "F23") (pin "6") (pinfunction "SCK_6") (pintype "passive"))
      (node (ref "F24") (pin "6") (pinfunction "SCK_6") (pintype "passive"))
      (node (ref "F25") (pin "6") (pinfunction "SCK_6") (pintype "passive"))
      (node (ref "F26") (pin "6") (pinfunction "SCK_6") (pintype "passive"))
      (node (ref "F27") (pin "6") (pinfunction "SCK_6") (pintype "passive"))
      (node (ref "F28") (pin "6") (pinfunction "SCK_6") (pintype "passive"))
      (node (ref "F29") (pin "6") (pinfunction "SCK_6") (pintype "passive"))
      (node (ref "F3") (pin "6") (pinfunction "SCK_6") (pintype "passive"))
      (node (ref "F30") (pin "6") (pinfunction "SCK_6") (pintype "passive"))
      (node (ref "F4") (pin "6") (pinfunction "SCK_6") (pintype "passive"))
      (node (ref "F5") (pin "6") (pinfunction "SCK_6") (pintype "passive"))
      (node (ref "F6") (pin "6") (pinfunction "SCK_6") (pintype "passive"))
      (node (ref "F7") (pin "6") (pinfunction "SCK_6") (pintype "passive"))
      (node (ref "F8") (pin "6") (pinfunction "SCK_6") (pintype "passive"))
      (node (ref "F9") (pin "6") (pinfunction "SCK_6") (pintype "passive"))
      (node (ref "Q1") (pin "2") (pinfunction "S_2") (pintype "bidirectional"))
      (node (ref "R1") (pin "2") (pinfunction "22_2") (pintype "passive"))
    )
    (net (code "100") (name "TEMP") (class "Default")
      (node (ref "J$4") (pin "11") (pinfunction "11_11") (pintype "passive"))
      (node (ref "U1") (pin "1") (pinfunction "DQ_1") (pintype "bidirectional"))
      (node (ref "U3") (pin "1") (pinfunction "DQ_1") (pintype "bidirectional"))
      (node (ref "U4") (pin "1") (pinfunction "DQ_1") (pintype "bidirectional"))
    )
    (net (code "101") (name "unconnected-(F1-~{WP}-Pad3)") (class "Default")
      (node (ref "F1") (pin "3") (pinfunction "~{WP}_3") (pintype "passive"))
    )
    (net (code "102") (name "unconnected-(F2-~{WP}-Pad3)") (class "Default")
      (node (ref "F2") (pin "3") (pinfunction "~{WP}_3") (pintype "passive"))
    )
    (net (code "103") (name "unconnected-(F3-~{WP}-Pad3)") (class "Default")
      (node (ref "F3") (pin "3") (pinfunction "~{WP}_3") (pintype "passive"))
    )
    (net (code "104") (name "unconnected-(F4-~{WP}-Pad3)") (class "Default")
      (node (ref "F4") (pin "3") (pinfunction "~{WP}_3") (pintype "passive"))
    )
    (net (code "105") (name "unconnected-(F5-~{WP}-Pad3)") (class "Default")
      (node (ref "F5") (pin "3") (pinfunction "~{WP}_3") (pintype "passive"))
    )
    (net (code "106") (name "unconnected-(F6-~{WP}-Pad3)") (class "Default")
      (node (ref "F6") (pin "3") (pinfunction "~{WP}_3") (pintype "passive"))
    )
    (net (code "107") (name "unconnected-(F7-~{WP}-Pad3)") (class "Default")
      (node (ref "F7") (pin "3") (pinfunction "~{WP}_3") (pintype "passive"))
    )
    (net (code "108") (name "unconnected-(F8-~{WP}-Pad3)") (class "Default")
      (node (ref "F8") (pin "3") (pinfunction "~{WP}_3") (pintype "passive"))
    )
    (net (code "109") (name "unconnected-(F9-~{WP}-Pad3)") (class "Default")
      (node (ref "F9") (pin "3") (pinfunction "~{WP}_3") (pintype "passive"))
    )
    (net (code "110") (name "unconnected-(F10-~{WP}-Pad3)") (class "Default")
      (node (ref "F10") (pin "3") (pinfunction "~{WP}_3") (pintype "passive"))
    )
    (net (code "111") (name "unconnected-(F11-~{WP}-Pad3)") (class "Default")
      (node (ref "F11") (pin "3") (pinfunction "~{WP}_3") (pintype "passive"))
    )
    (net (code "112") (name "unconnected-(F12-~{WP}-Pad3)") (class "Default")
      (node (ref "F12") (pin "3") (pinfunction "~{WP}_3") (pintype "passive"))
    )
    (net (code "113") (name "unconnected-(F13-~{WP}-Pad3)") (class "Default")
      (node (ref "F13") (pin "3") (pinfunction "~{WP}_3") (pintype "passive"))
    )
    (net (code "114") (name "unconnected-(F14-~{WP}-Pad3)") (class "Default")
      (node (ref "F14") (pin "3") (pinfunction "~{WP}_3") (pintype "passive"))
    )
    (net (code "115") (name "unconnected-(F15-~{WP}-Pad3)") (class "Default")
      (node (ref "F15") (pin "3") (pinfunction "~{WP}_3") (pintype "passive"))
    )
    (net (code "116") (name "unconnected-(F16-~{WP}-Pad3)") (class "Default")
      (node (ref "F16") (pin "3") (pinfunction "~{WP}_3") (pintype "passive"))
    )
    (net (code "117") (name "unconnected-(F17-~{WP}-Pad3)") (class "Default")
      (node (ref "F17") (pin "3") (pinfunction "~{WP}_3") (pintype "passive"))
    )
    (net (code "118") (name "unconnected-(F18-~{WP}-Pad3)") (class "Default")
      (node (ref "F18") (pin "3") (pinfunction "~{WP}_3") (pintype "passive"))
    )
    (net (code "119") (name "unconnected-(F19-~{WP}-Pad3)") (class "Default")
      (node (ref "F19") (pin "3") (pinfunction "~{WP}_3") (pintype "passive"))
    )
    (net (code "120") (name "unconnected-(F20-~{WP}-Pad3)") (class "Default")
      (node (ref "F20") (pin "3") (pinfunction "~{WP}_3") (pintype "passive"))
    )
    (net (code "121") (name "unconnected-(F21-~{WP}-Pad3)") (class "Default")
      (node (ref "F21") (pin "3") (pinfunction "~{WP}_3") (pintype "passive"))
    )
    (net (code "122") (name "unconnected-(F22-~{WP}-Pad3)") (class "Default")
      (node (ref "F22") (pin "3") (pinfunction "~{WP}_3") (pintype "passive"))
    )
    (net (code "123") (name "unconnected-(F23-~{WP}-Pad3)") (class "Default")
      (node (ref "F23") (pin "3") (pinfunction "~{WP}_3") (pintype "passive"))
    )
    (net (code "124") (name "unconnected-(F24-~{WP}-Pad3)") (class "Default")
      (node (ref "F24") (pin "3") (pinfunction "~{WP}_3") (pintype "passive"))
    )
    (net (code "125") (name "unconnected-(F25-~{WP}-Pad3)") (class "Default")
      (node (ref "F25") (pin "3") (pinfunction "~{WP}_3") (pintype "passive"))
    )
    (net (code "126") (name "unconnected-(F26-~{WP}-Pad3)") (class "Default")
      (node (ref "F26") (pin "3") (pinfunction "~{WP}_3") (pintype "passive"))
    )
    (net (code "127") (name "unconnected-(F27-~{WP}-Pad3)") (class "Default")
      (node (ref "F27") (pin "3") (pinfunction "~{WP}_3") (pintype "passive"))
    )
    (net (code "128") (name "unconnected-(F28-~{WP}-Pad3)") (class "Default")
      (node (ref "F28") (pin "3") (pinfunction "~{WP}_3") (pintype "passive"))
    )
    (net (code "129") (name "unconnected-(F29-~{WP}-Pad3)") (class "Default")
      (node (ref "F29") (pin "3") (pinfunction "~{WP}_3") (pintype "passive"))
    )
    (net (code "130") (name "unconnected-(F30-~{WP}-Pad3)") (class "Default")
      (node (ref "F30") (pin "3") (pinfunction "~{WP}_3") (pintype "passive"))
    )
    (net (code "131") (name "unconnected-(H1-MOUNT-PadB3,2)") (class "Default")
      (node (ref "H1") (pin "B3,2") (pinfunction "MOUNT_B3,2") (pintype "passive"))
    )
    (net (code "132") (name "unconnected-(H2-MOUNT-PadB3,2)") (class "Default")
      (node (ref "H2") (pin "B3,2") (pinfunction "MOUNT_B3,2") (pintype "passive"))
    )
    (net (code "133") (name "unconnected-(H3-MOUNT-PadB3,2)") (class "Default")
      (node (ref "H3") (pin "B3,2") (pinfunction "MOUNT_B3,2") (pintype "passive"))
    )
    (net (code "134") (name "unconnected-(H4-MOUNT-PadB3,2)") (class "Default")
      (node (ref "H4") (pin "B3,2") (pinfunction "MOUNT_B3,2") (pintype "passive"))
    )
    (net (code "135") (name "unconnected-(J$4-Pad4)") (class "Default")
      (node (ref "J$4") (pin "4") (pinfunction "4_4") (pintype "passive"))
    )
    (net (code "136") (name "unconnected-(J$4-Pad5)") (class "Default")
      (node (ref "J$4") (pin "5") (pinfunction "5_5") (pintype "passive"))
    )
    (net (code "137") (name "unconnected-(J$4-Pad6)") (class "Default")
      (node (ref "J$4") (pin "6") (pinfunction "6_6") (pintype "passive"))
    )
    (net (code "138") (name "unconnected-(J$4-Pad7)") (class "Default")
      (node (ref "J$4") (pin "7") (pinfunction "7_7") (pintype "passive"))
    )
    (net (code "139") (name "unconnected-(J$4-Pad8)") (class "Default")
      (node (ref "J$4") (pin "8") (pinfunction "8_8") (pintype "passive"))
    )
    (net (code "140") (name "unconnected-(J$4-Pad9)") (class "Default")
      (node (ref "J$4") (pin "9") (pinfunction "9_9") (pintype "passive"))
    )
    (net (code "141") (name "unconnected-(J$4-Pad10)") (class "Default")
      (node (ref "J$4") (pin "10") (pinfunction "10_10") (pintype "passive"))
    )
    (net (code "142") (name "unconnected-(U2-P4-PadNC{slash}ADJ)") (class "Default")
      (node (ref "U2") (pin "NC/ADJ") (pinfunction "P4_NC/ADJ") (pintype "bidirectional"))
    )
  )
)
